# icyradio-exp-mmw-int-rf.net
KiCad netlist of a schematic drawn in EAGLE
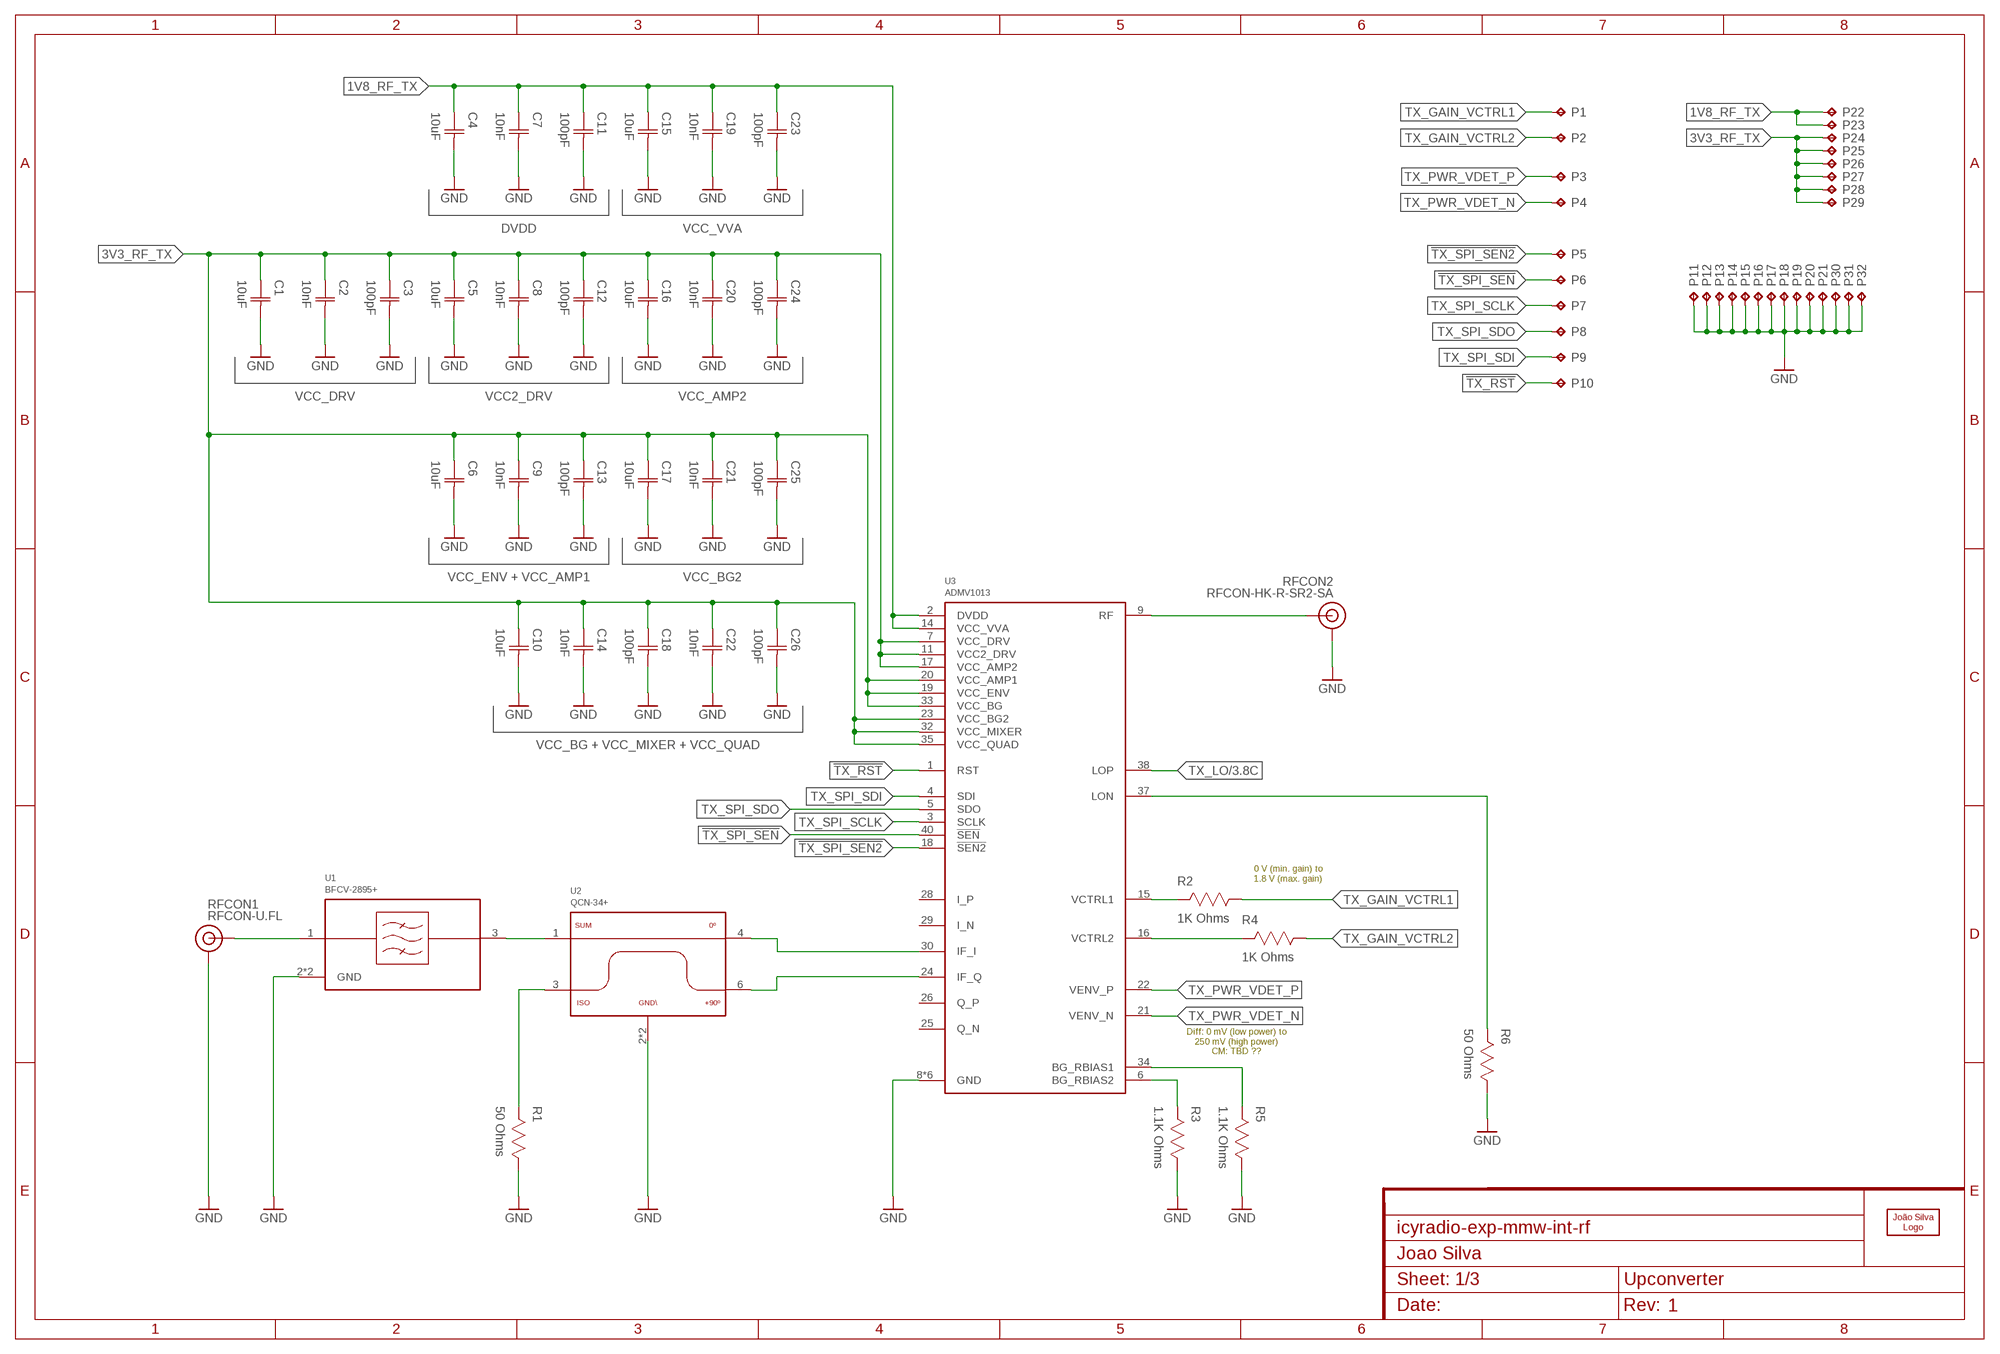
[diagram p0: schematic, sheet 1]
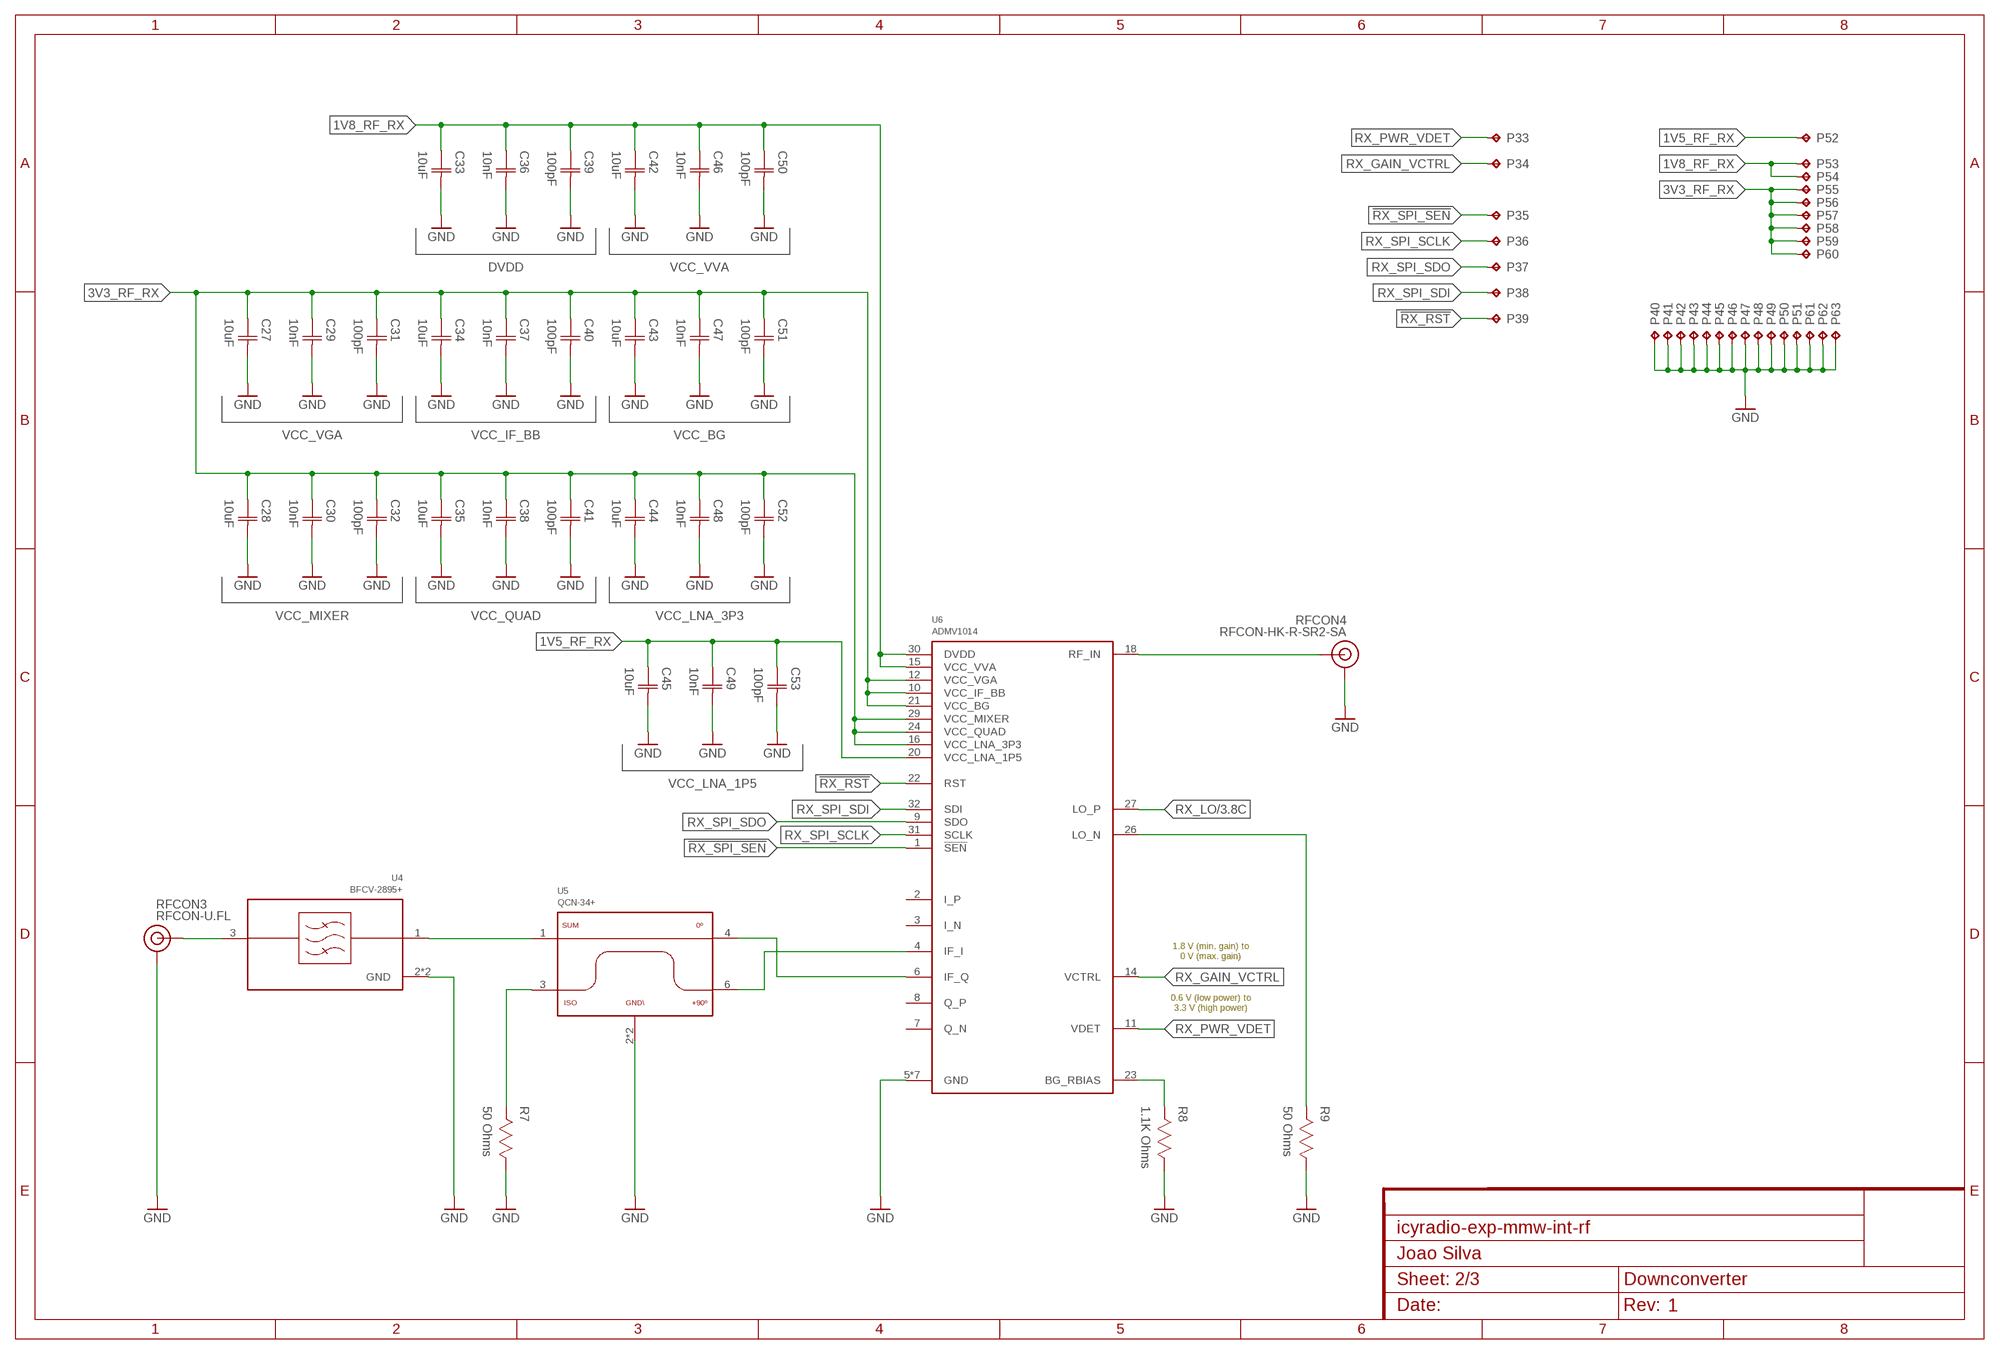
[diagram p1: schematic, sheet 2]
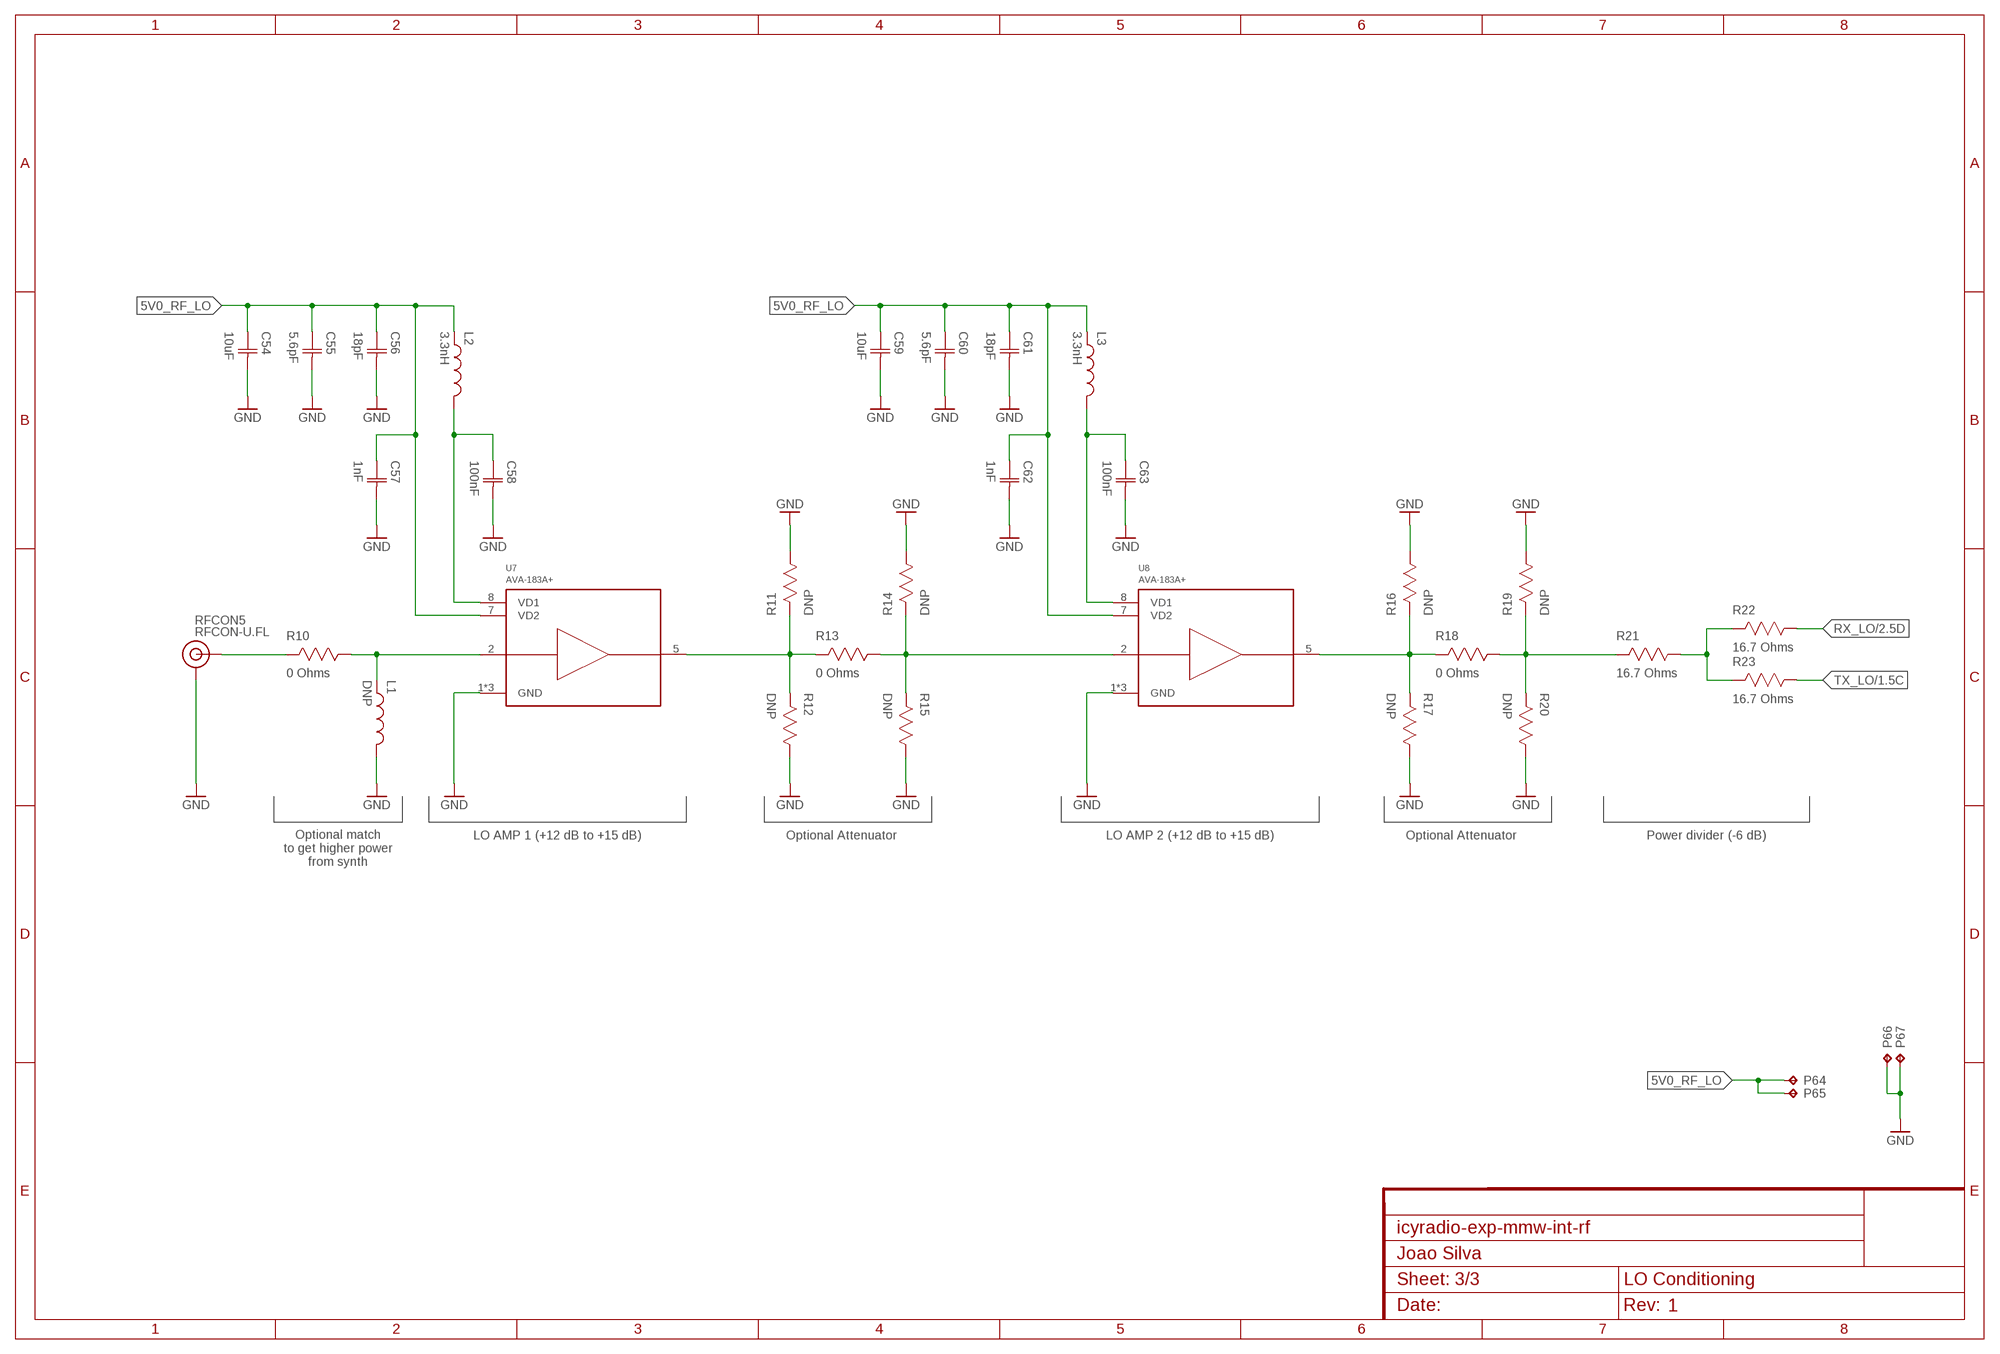
[diagram p2: schematic, sheet 3]

(export (version "E")
  (design (tool "Eeschema 10.0.6"))
  (components
    (comp (ref "C54")
      (value "10uF")
      (footprint "eagle-import:CAP0402")
      (libsource (lib "eagle-import") (part "CAPACITOR-0402"))
    )
    (comp (ref "C55")
      (value "5.6pF")
      (footprint "eagle-import:CAP0402")
      (libsource (lib "eagle-import") (part "CAPACITOR-0402"))
    )
    (comp (ref "C56")
      (value "18pF")
      (footprint "eagle-import:CAP0402")
      (libsource (lib "eagle-import") (part "CAPACITOR-0402"))
    )
    (comp (ref "C57")
      (value "1nF")
      (footprint "eagle-import:CAP0402")
      (libsource (lib "eagle-import") (part "CAPACITOR-0402"))
    )
    (comp (ref "C58")
      (value "100nF")
      (footprint "eagle-import:CAP0402")
      (libsource (lib "eagle-import") (part "CAPACITOR-0402"))
    )
    (comp (ref "C59")
      (value "10uF")
      (footprint "eagle-import:CAP0402")
      (libsource (lib "eagle-import") (part "CAPACITOR-0402"))
    )
    (comp (ref "C60")
      (value "5.6pF")
      (footprint "eagle-import:CAP0402")
      (libsource (lib "eagle-import") (part "CAPACITOR-0402"))
    )
    (comp (ref "C61")
      (value "18pF")
      (footprint "eagle-import:CAP0402")
      (libsource (lib "eagle-import") (part "CAPACITOR-0402"))
    )
    (comp (ref "C62")
      (value "1nF")
      (footprint "eagle-import:CAP0402")
      (libsource (lib "eagle-import") (part "CAPACITOR-0402"))
    )
    (comp (ref "C63")
      (value "100nF")
      (footprint "eagle-import:CAP0402")
      (libsource (lib "eagle-import") (part "CAPACITOR-0402"))
    )
    (comp (ref "L1")
      (value "DNP")
      (footprint "eagle-import:IND0402")
      (libsource (lib "eagle-import") (part "INDUCTOR-0402"))
    )
    (comp (ref "L2")
      (value "3.3nH")
      (footprint "eagle-import:IND0402")
      (libsource (lib "eagle-import") (part "INDUCTOR-0402"))
    )
    (comp (ref "L3")
      (value "3.3nH")
      (footprint "eagle-import:IND0402")
      (libsource (lib "eagle-import") (part "INDUCTOR-0402"))
    )
    (comp (ref "P64")
      (value "CHOLE-0.9MM-SS")
      (footprint "eagle-import:CAST_HOLE_0P9MM_SS")
      (libsource (lib "eagle-import") (part "CHOLE-0.9MM-SS"))
    )
    (comp (ref "P65")
      (value "CHOLE-0.9MM-SS")
      (footprint "eagle-import:CAST_HOLE_0P9MM_SS")
      (libsource (lib "eagle-import") (part "CHOLE-0.9MM-SS"))
    )
    (comp (ref "P66")
      (value "CHOLE-0.9MM-DS")
      (footprint "eagle-import:CAST_HOLE_0P9MM_DS")
      (libsource (lib "eagle-import") (part "CHOLE-0.9MM-DS"))
    )
    (comp (ref "P67")
      (value "CHOLE-0.9MM-DS")
      (footprint "eagle-import:CAST_HOLE_0P9MM_DS")
      (libsource (lib "eagle-import") (part "CHOLE-0.9MM-DS"))
    )
    (comp (ref "R10")
      (value "0 Ohms")
      (footprint "eagle-import:RES0402")
      (libsource (lib "eagle-import") (part "RESISTOR-0402"))
    )
    (comp (ref "R11")
      (value "DNP")
      (footprint "eagle-import:RES0402")
      (libsource (lib "eagle-import") (part "RESISTOR-0402"))
    )
    (comp (ref "R12")
      (value "DNP")
      (footprint "eagle-import:RES0402")
      (libsource (lib "eagle-import") (part "RESISTOR-0402"))
    )
    (comp (ref "R13")
      (value "0 Ohms")
      (footprint "eagle-import:RES0402")
      (libsource (lib "eagle-import") (part "RESISTOR-0402"))
    )
    (comp (ref "R14")
      (value "DNP")
      (footprint "eagle-import:RES0402")
      (libsource (lib "eagle-import") (part "RESISTOR-0402"))
    )
    (comp (ref "R15")
      (value "DNP")
      (footprint "eagle-import:RES0402")
      (libsource (lib "eagle-import") (part "RESISTOR-0402"))
    )
    (comp (ref "R16")
      (value "DNP")
      (footprint "eagle-import:RES0402")
      (libsource (lib "eagle-import") (part "RESISTOR-0402"))
    )
    (comp (ref "R17")
      (value "DNP")
      (footprint "eagle-import:RES0402")
      (libsource (lib "eagle-import") (part "RESISTOR-0402"))
    )
    (comp (ref "R18")
      (value "0 Ohms")
      (footprint "eagle-import:RES0402")
      (libsource (lib "eagle-import") (part "RESISTOR-0402"))
    )
    (comp (ref "R19")
      (value "DNP")
      (footprint "eagle-import:RES0402")
      (libsource (lib "eagle-import") (part "RESISTOR-0402"))
    )
    (comp (ref "R20")
      (value "DNP")
      (footprint "eagle-import:RES0402")
      (libsource (lib "eagle-import") (part "RESISTOR-0402"))
    )
    (comp (ref "R21")
      (value "16.7 Ohms")
      (footprint "eagle-import:RES0402")
      (libsource (lib "eagle-import") (part "RESISTOR-0402"))
    )
    (comp (ref "R22")
      (value "16.7 Ohms")
      (footprint "eagle-import:RES0402")
      (libsource (lib "eagle-import") (part "RESISTOR-0402"))
    )
    (comp (ref "R23")
      (value "16.7 Ohms")
      (footprint "eagle-import:RES0402")
      (libsource (lib "eagle-import") (part "RESISTOR-0402"))
    )
    (comp (ref "RFCON5")
      (value "RFCON-U.FL")
      (footprint "eagle-import:U.FL")
      (libsource (lib "eagle-import") (part "RFCON-U.FL"))
    )
    (comp (ref "U7")
      (value "AVA-183A+")
      (footprint "eagle-import:DQ849")
      (libsource (lib "eagle-import") (part "AVA-183A+"))
    )
    (comp (ref "U8")
      (value "AVA-183A+")
      (footprint "eagle-import:DQ849")
      (libsource (lib "eagle-import") (part "AVA-183A+"))
    )
    (comp (ref "C1")
      (value "10uF")
      (footprint "eagle-import:CAP0402")
      (libsource (lib "eagle-import") (part "CAPACITOR-0402"))
    )
    (comp (ref "C2")
      (value "10nF")
      (footprint "eagle-import:CAP0402")
      (libsource (lib "eagle-import") (part "CAPACITOR-0402"))
    )
    (comp (ref "C3")
      (value "100pF")
      (footprint "eagle-import:CAP0402")
      (libsource (lib "eagle-import") (part "CAPACITOR-0402"))
    )
    (comp (ref "C4")
      (value "10uF")
      (footprint "eagle-import:CAP0402")
      (libsource (lib "eagle-import") (part "CAPACITOR-0402"))
    )
    (comp (ref "C5")
      (value "10uF")
      (footprint "eagle-import:CAP0402")
      (libsource (lib "eagle-import") (part "CAPACITOR-0402"))
    )
    (comp (ref "C6")
      (value "10uF")
      (footprint "eagle-import:CAP0402")
      (libsource (lib "eagle-import") (part "CAPACITOR-0402"))
    )
    (comp (ref "C7")
      (value "10nF")
      (footprint "eagle-import:CAP0402")
      (libsource (lib "eagle-import") (part "CAPACITOR-0402"))
    )
    (comp (ref "C8")
      (value "10nF")
      (footprint "eagle-import:CAP0402")
      (libsource (lib "eagle-import") (part "CAPACITOR-0402"))
    )
    (comp (ref "C9")
      (value "10nF")
      (footprint "eagle-import:CAP0402")
      (libsource (lib "eagle-import") (part "CAPACITOR-0402"))
    )
    (comp (ref "C10")
      (value "10uF")
      (footprint "eagle-import:CAP0402")
      (libsource (lib "eagle-import") (part "CAPACITOR-0402"))
    )
    (comp (ref "C11")
      (value "100pF")
      (footprint "eagle-import:CAP0402")
      (libsource (lib "eagle-import") (part "CAPACITOR-0402"))
    )
    (comp (ref "C12")
      (value "100pF")
      (footprint "eagle-import:CAP0402")
      (libsource (lib "eagle-import") (part "CAPACITOR-0402"))
    )
    (comp (ref "C13")
      (value "100pF")
      (footprint "eagle-import:CAP0402")
      (libsource (lib "eagle-import") (part "CAPACITOR-0402"))
    )
    (comp (ref "C14")
      (value "10nF")
      (footprint "eagle-import:CAP0402")
      (libsource (lib "eagle-import") (part "CAPACITOR-0402"))
    )
    (comp (ref "C15")
      (value "10uF")
      (footprint "eagle-import:CAP0402")
      (libsource (lib "eagle-import") (part "CAPACITOR-0402"))
    )
    (comp (ref "C16")
      (value "10uF")
      (footprint "eagle-import:CAP0402")
      (libsource (lib "eagle-import") (part "CAPACITOR-0402"))
    )
    (comp (ref "C17")
      (value "10uF")
      (footprint "eagle-import:CAP0402")
      (libsource (lib "eagle-import") (part "CAPACITOR-0402"))
    )
    (comp (ref "C18")
      (value "100pF")
      (footprint "eagle-import:CAP0402")
      (libsource (lib "eagle-import") (part "CAPACITOR-0402"))
    )
    (comp (ref "C19")
      (value "10nF")
      (footprint "eagle-import:CAP0402")
      (libsource (lib "eagle-import") (part "CAPACITOR-0402"))
    )
    (comp (ref "C20")
      (value "10nF")
      (footprint "eagle-import:CAP0402")
      (libsource (lib "eagle-import") (part "CAPACITOR-0402"))
    )
    (comp (ref "C21")
      (value "10nF")
      (footprint "eagle-import:CAP0402")
      (libsource (lib "eagle-import") (part "CAPACITOR-0402"))
    )
    (comp (ref "C22")
      (value "10nF")
      (footprint "eagle-import:CAP0402")
      (libsource (lib "eagle-import") (part "CAPACITOR-0402"))
    )
    (comp (ref "C23")
      (value "100pF")
      (footprint "eagle-import:CAP0402")
      (libsource (lib "eagle-import") (part "CAPACITOR-0402"))
    )
    (comp (ref "C24")
      (value "100pF")
      (footprint "eagle-import:CAP0402")
      (libsource (lib "eagle-import") (part "CAPACITOR-0402"))
    )
    (comp (ref "C25")
      (value "100pF")
      (footprint "eagle-import:CAP0402")
      (libsource (lib "eagle-import") (part "CAPACITOR-0402"))
    )
    (comp (ref "C26")
      (value "100pF")
      (footprint "eagle-import:CAP0402")
      (libsource (lib "eagle-import") (part "CAPACITOR-0402"))
    )
    (comp (ref "LOGO1")
      (value "JSILVA-5MM")
      (footprint "eagle-import:JSILVA_5MM")
      (libsource (lib "eagle-import") (part "JSILVA-5MM"))
    )
    (comp (ref "P1")
      (value "CHOLE-0.9MM-SS")
      (footprint "eagle-import:CAST_HOLE_0P9MM_SS")
      (libsource (lib "eagle-import") (part "CHOLE-0.9MM-SS"))
    )
    (comp (ref "P2")
      (value "CHOLE-0.9MM-SS")
      (footprint "eagle-import:CAST_HOLE_0P9MM_SS")
      (libsource (lib "eagle-import") (part "CHOLE-0.9MM-SS"))
    )
    (comp (ref "P3")
      (value "CHOLE-0.9MM-SS")
      (footprint "eagle-import:CAST_HOLE_0P9MM_SS")
      (libsource (lib "eagle-import") (part "CHOLE-0.9MM-SS"))
    )
    (comp (ref "P4")
      (value "CHOLE-0.9MM-SS")
      (footprint "eagle-import:CAST_HOLE_0P9MM_SS")
      (libsource (lib "eagle-import") (part "CHOLE-0.9MM-SS"))
    )
    (comp (ref "P5")
      (value "CHOLE-0.9MM-SS")
      (footprint "eagle-import:CAST_HOLE_0P9MM_SS")
      (libsource (lib "eagle-import") (part "CHOLE-0.9MM-SS"))
    )
    (comp (ref "P6")
      (value "CHOLE-0.9MM-SS")
      (footprint "eagle-import:CAST_HOLE_0P9MM_SS")
      (libsource (lib "eagle-import") (part "CHOLE-0.9MM-SS"))
    )
    (comp (ref "P7")
      (value "CHOLE-0.9MM-SS")
      (footprint "eagle-import:CAST_HOLE_0P9MM_SS")
      (libsource (lib "eagle-import") (part "CHOLE-0.9MM-SS"))
    )
    (comp (ref "P8")
      (value "CHOLE-0.9MM-SS")
      (footprint "eagle-import:CAST_HOLE_0P9MM_SS")
      (libsource (lib "eagle-import") (part "CHOLE-0.9MM-SS"))
    )
    (comp (ref "P9")
      (value "CHOLE-0.9MM-SS")
      (footprint "eagle-import:CAST_HOLE_0P9MM_SS")
      (libsource (lib "eagle-import") (part "CHOLE-0.9MM-SS"))
    )
    (comp (ref "P10")
      (value "CHOLE-0.9MM-SS")
      (footprint "eagle-import:CAST_HOLE_0P9MM_SS")
      (libsource (lib "eagle-import") (part "CHOLE-0.9MM-SS"))
    )
    (comp (ref "P11")
      (value "CHOLE-0.9MM-DS")
      (footprint "eagle-import:CAST_HOLE_0P9MM_DS")
      (libsource (lib "eagle-import") (part "CHOLE-0.9MM-DS"))
    )
    (comp (ref "P12")
      (value "CHOLE-0.9MM-DS")
      (footprint "eagle-import:CAST_HOLE_0P9MM_DS")
      (libsource (lib "eagle-import") (part "CHOLE-0.9MM-DS"))
    )
    (comp (ref "P13")
      (value "CHOLE-0.9MM-DS")
      (footprint "eagle-import:CAST_HOLE_0P9MM_DS")
      (libsource (lib "eagle-import") (part "CHOLE-0.9MM-DS"))
    )
    (comp (ref "P14")
      (value "CHOLE-0.9MM-DS")
      (footprint "eagle-import:CAST_HOLE_0P9MM_DS")
      (libsource (lib "eagle-import") (part "CHOLE-0.9MM-DS"))
    )
    (comp (ref "P15")
      (value "CHOLE-0.9MM-DS")
      (footprint "eagle-import:CAST_HOLE_0P9MM_DS")
      (libsource (lib "eagle-import") (part "CHOLE-0.9MM-DS"))
    )
    (comp (ref "P16")
      (value "CHOLE-0.9MM-DS")
      (footprint "eagle-import:CAST_HOLE_0P9MM_DS")
      (libsource (lib "eagle-import") (part "CHOLE-0.9MM-DS"))
    )
    (comp (ref "P17")
      (value "CHOLE-0.9MM-DS")
      (footprint "eagle-import:CAST_HOLE_0P9MM_DS")
      (libsource (lib "eagle-import") (part "CHOLE-0.9MM-DS"))
    )
    (comp (ref "P18")
      (value "CHOLE-0.9MM-DS")
      (footprint "eagle-import:CAST_HOLE_0P9MM_DS")
      (libsource (lib "eagle-import") (part "CHOLE-0.9MM-DS"))
    )
    (comp (ref "P19")
      (value "CHOLE-0.9MM-DS")
      (footprint "eagle-import:CAST_HOLE_0P9MM_DS")
      (libsource (lib "eagle-import") (part "CHOLE-0.9MM-DS"))
    )
    (comp (ref "P20")
      (value "CHOLE-0.9MM-DS")
      (footprint "eagle-import:CAST_HOLE_0P9MM_DS")
      (libsource (lib "eagle-import") (part "CHOLE-0.9MM-DS"))
    )
    (comp (ref "P21")
      (value "CHOLE-0.9MM-DS")
      (footprint "eagle-import:CAST_HOLE_0P9MM_DS")
      (libsource (lib "eagle-import") (part "CHOLE-0.9MM-DS"))
    )
    (comp (ref "P22")
      (value "CHOLE-0.9MM-SS")
      (footprint "eagle-import:CAST_HOLE_0P9MM_SS")
      (libsource (lib "eagle-import") (part "CHOLE-0.9MM-SS"))
    )
    (comp (ref "P23")
      (value "CHOLE-0.9MM-SS")
      (footprint "eagle-import:CAST_HOLE_0P9MM_SS")
      (libsource (lib "eagle-import") (part "CHOLE-0.9MM-SS"))
    )
    (comp (ref "P24")
      (value "CHOLE-0.9MM-SS")
      (footprint "eagle-import:CAST_HOLE_0P9MM_SS")
      (libsource (lib "eagle-import") (part "CHOLE-0.9MM-SS"))
    )
    (comp (ref "P25")
      (value "CHOLE-0.9MM-SS")
      (footprint "eagle-import:CAST_HOLE_0P9MM_SS")
      (libsource (lib "eagle-import") (part "CHOLE-0.9MM-SS"))
    )
    (comp (ref "P26")
      (value "CHOLE-0.9MM-SS")
      (footprint "eagle-import:CAST_HOLE_0P9MM_SS")
      (libsource (lib "eagle-import") (part "CHOLE-0.9MM-SS"))
    )
    (comp (ref "P27")
      (value "CHOLE-0.9MM-SS")
      (footprint "eagle-import:CAST_HOLE_0P9MM_SS")
      (libsource (lib "eagle-import") (part "CHOLE-0.9MM-SS"))
    )
    (comp (ref "P28")
      (value "CHOLE-0.9MM-SS")
      (footprint "eagle-import:CAST_HOLE_0P9MM_SS")
      (libsource (lib "eagle-import") (part "CHOLE-0.9MM-SS"))
    )
    (comp (ref "P29")
      (value "CHOLE-0.9MM-SS")
      (footprint "eagle-import:CAST_HOLE_0P9MM_SS")
      (libsource (lib "eagle-import") (part "CHOLE-0.9MM-SS"))
    )
    (comp (ref "P30")
      (value "CHOLE-0.9MM-DS")
      (footprint "eagle-import:CAST_HOLE_0P9MM_DS")
      (libsource (lib "eagle-import") (part "CHOLE-0.9MM-DS"))
    )
    (comp (ref "P31")
      (value "CHOLE-0.9MM-DS")
      (footprint "eagle-import:CAST_HOLE_0P9MM_DS")
      (libsource (lib "eagle-import") (part "CHOLE-0.9MM-DS"))
    )
    (comp (ref "P32")
      (value "CHOLE-0.9MM-DS")
      (footprint "eagle-import:CAST_HOLE_0P9MM_DS")
      (libsource (lib "eagle-import") (part "CHOLE-0.9MM-DS"))
    )
    (comp (ref "R1")
      (value "50 Ohms")
      (footprint "eagle-import:RES0402")
      (libsource (lib "eagle-import") (part "RESISTOR-0402"))
    )
    (comp (ref "R2")
      (value "1K Ohms")
      (footprint "eagle-import:RES0402")
      (libsource (lib "eagle-import") (part "RESISTOR-0402"))
    )
    (comp (ref "R3")
      (value "1.1K Ohms")
      (footprint "eagle-import:RES0402")
      (libsource (lib "eagle-import") (part "RESISTOR-0402"))
    )
    (comp (ref "R4")
      (value "1K Ohms")
      (footprint "eagle-import:RES0402")
      (libsource (lib "eagle-import") (part "RESISTOR-0402"))
    )
    (comp (ref "R5")
      (value "1.1K Ohms")
      (footprint "eagle-import:RES0402")
      (libsource (lib "eagle-import") (part "RESISTOR-0402"))
    )
    (comp (ref "R6")
      (value "50 Ohms")
      (footprint "eagle-import:RES0402")
      (libsource (lib "eagle-import") (part "RESISTOR-0402"))
    )
    (comp (ref "RFCON1")
      (value "RFCON-U.FL")
      (footprint "eagle-import:U.FL")
      (libsource (lib "eagle-import") (part "RFCON-U.FL"))
    )
    (comp (ref "RFCON2")
      (value "RFCON-HK-R-SR2-SA")
      (footprint "eagle-import:HK-R-SR2-SA")
      (libsource (lib "eagle-import") (part "RFCON-HK-R-SR2-SA"))
    )
    (comp (ref "U1")
      (value "BFCV-2895+")
      (footprint "eagle-import:JV1210C")
      (libsource (lib "eagle-import") (part "BFCV-+2895"))
    )
    (comp (ref "U2")
      (value "QCN-34+")
      (footprint "eagle-import:FV1206-1")
      (libsource (lib "eagle-import") (part "QCN-34+"))
    )
    (comp (ref "U3")
      (value "ADMV1013")
      (footprint "eagle-import:LGA40")
      (libsource (lib "eagle-import") (part "ADMV1013"))
    )
    (comp (ref "C27")
      (value "10uF")
      (footprint "eagle-import:CAP0402")
      (libsource (lib "eagle-import") (part "CAPACITOR-0402"))
    )
    (comp (ref "C28")
      (value "10uF")
      (footprint "eagle-import:CAP0402")
      (libsource (lib "eagle-import") (part "CAPACITOR-0402"))
    )
    (comp (ref "C29")
      (value "10nF")
      (footprint "eagle-import:CAP0402")
      (libsource (lib "eagle-import") (part "CAPACITOR-0402"))
    )
    (comp (ref "C30")
      (value "10nF")
      (footprint "eagle-import:CAP0402")
      (libsource (lib "eagle-import") (part "CAPACITOR-0402"))
    )
    (comp (ref "C31")
      (value "100pF")
      (footprint "eagle-import:CAP0402")
      (libsource (lib "eagle-import") (part "CAPACITOR-0402"))
    )
    (comp (ref "C32")
      (value "100pF")
      (footprint "eagle-import:CAP0402")
      (libsource (lib "eagle-import") (part "CAPACITOR-0402"))
    )
    (comp (ref "C33")
      (value "10uF")
      (footprint "eagle-import:CAP0402")
      (libsource (lib "eagle-import") (part "CAPACITOR-0402"))
    )
    (comp (ref "C34")
      (value "10uF")
      (footprint "eagle-import:CAP0402")
      (libsource (lib "eagle-import") (part "CAPACITOR-0402"))
    )
    (comp (ref "C35")
      (value "10uF")
      (footprint "eagle-import:CAP0402")
      (libsource (lib "eagle-import") (part "CAPACITOR-0402"))
    )
    (comp (ref "C36")
      (value "10nF")
      (footprint "eagle-import:CAP0402")
      (libsource (lib "eagle-import") (part "CAPACITOR-0402"))
    )
    (comp (ref "C37")
      (value "10nF")
      (footprint "eagle-import:CAP0402")
      (libsource (lib "eagle-import") (part "CAPACITOR-0402"))
    )
    (comp (ref "C38")
      (value "10nF")
      (footprint "eagle-import:CAP0402")
      (libsource (lib "eagle-import") (part "CAPACITOR-0402"))
    )
    (comp (ref "C39")
      (value "100pF")
      (footprint "eagle-import:CAP0402")
      (libsource (lib "eagle-import") (part "CAPACITOR-0402"))
    )
    (comp (ref "C40")
      (value "100pF")
      (footprint "eagle-import:CAP0402")
      (libsource (lib "eagle-import") (part "CAPACITOR-0402"))
    )
    (comp (ref "C41")
      (value "100pF")
      (footprint "eagle-import:CAP0402")
      (libsource (lib "eagle-import") (part "CAPACITOR-0402"))
    )
    (comp (ref "C42")
      (value "10uF")
      (footprint "eagle-import:CAP0402")
      (libsource (lib "eagle-import") (part "CAPACITOR-0402"))
    )
    (comp (ref "C43")
      (value "10uF")
      (footprint "eagle-import:CAP0402")
      (libsource (lib "eagle-import") (part "CAPACITOR-0402"))
    )
    (comp (ref "C44")
      (value "10uF")
      (footprint "eagle-import:CAP0402")
      (libsource (lib "eagle-import") (part "CAPACITOR-0402"))
    )
    (comp (ref "C45")
      (value "10uF")
      (footprint "eagle-import:CAP0402")
      (libsource (lib "eagle-import") (part "CAPACITOR-0402"))
    )
    (comp (ref "C46")
      (value "10nF")
      (footprint "eagle-import:CAP0402")
      (libsource (lib "eagle-import") (part "CAPACITOR-0402"))
    )
    (comp (ref "C47")
      (value "10nF")
      (footprint "eagle-import:CAP0402")
      (libsource (lib "eagle-import") (part "CAPACITOR-0402"))
    )
    (comp (ref "C48")
      (value "10nF")
      (footprint "eagle-import:CAP0402")
      (libsource (lib "eagle-import") (part "CAPACITOR-0402"))
    )
    (comp (ref "C49")
      (value "10nF")
      (footprint "eagle-import:CAP0402")
      (libsource (lib "eagle-import") (part "CAPACITOR-0402"))
    )
    (comp (ref "C50")
      (value "100pF")
      (footprint "eagle-import:CAP0402")
      (libsource (lib "eagle-import") (part "CAPACITOR-0402"))
    )
    (comp (ref "C51")
      (value "100pF")
      (footprint "eagle-import:CAP0402")
      (libsource (lib "eagle-import") (part "CAPACITOR-0402"))
    )
    (comp (ref "C52")
      (value "100pF")
      (footprint "eagle-import:CAP0402")
      (libsource (lib "eagle-import") (part "CAPACITOR-0402"))
    )
    (comp (ref "C53")
      (value "100pF")
      (footprint "eagle-import:CAP0402")
      (libsource (lib "eagle-import") (part "CAPACITOR-0402"))
    )
    (comp (ref "P33")
      (value "CHOLE-0.9MM-SS")
      (footprint "eagle-import:CAST_HOLE_0P9MM_SS")
      (libsource (lib "eagle-import") (part "CHOLE-0.9MM-SS"))
    )
    (comp (ref "P34")
      (value "CHOLE-0.9MM-SS")
      (footprint "eagle-import:CAST_HOLE_0P9MM_SS")
      (libsource (lib "eagle-import") (part "CHOLE-0.9MM-SS"))
    )
    (comp (ref "P35")
      (value "CHOLE-0.9MM-SS")
      (footprint "eagle-import:CAST_HOLE_0P9MM_SS")
      (libsource (lib "eagle-import") (part "CHOLE-0.9MM-SS"))
    )
    (comp (ref "P36")
      (value "CHOLE-0.9MM-SS")
      (footprint "eagle-import:CAST_HOLE_0P9MM_SS")
      (libsource (lib "eagle-import") (part "CHOLE-0.9MM-SS"))
    )
    (comp (ref "P37")
      (value "CHOLE-0.9MM-SS")
      (footprint "eagle-import:CAST_HOLE_0P9MM_SS")
      (libsource (lib "eagle-import") (part "CHOLE-0.9MM-SS"))
    )
    (comp (ref "P38")
      (value "CHOLE-0.9MM-SS")
      (footprint "eagle-import:CAST_HOLE_0P9MM_SS")
      (libsource (lib "eagle-import") (part "CHOLE-0.9MM-SS"))
    )
    (comp (ref "P39")
      (value "CHOLE-0.9MM-SS")
      (footprint "eagle-import:CAST_HOLE_0P9MM_SS")
      (libsource (lib "eagle-import") (part "CHOLE-0.9MM-SS"))
    )
    (comp (ref "P40")
      (value "CHOLE-0.9MM-DS")
      (footprint "eagle-import:CAST_HOLE_0P9MM_DS")
      (libsource (lib "eagle-import") (part "CHOLE-0.9MM-DS"))
    )
    (comp (ref "P41")
      (value "CHOLE-0.9MM-DS")
      (footprint "eagle-import:CAST_HOLE_0P9MM_DS")
      (libsource (lib "eagle-import") (part "CHOLE-0.9MM-DS"))
    )
    (comp (ref "P42")
      (value "CHOLE-0.9MM-DS")
      (footprint "eagle-import:CAST_HOLE_0P9MM_DS")
      (libsource (lib "eagle-import") (part "CHOLE-0.9MM-DS"))
    )
    (comp (ref "P43")
      (value "CHOLE-0.9MM-DS")
      (footprint "eagle-import:CAST_HOLE_0P9MM_DS")
      (libsource (lib "eagle-import") (part "CHOLE-0.9MM-DS"))
    )
    (comp (ref "P44")
      (value "CHOLE-0.9MM-DS")
      (footprint "eagle-import:CAST_HOLE_0P9MM_DS")
      (libsource (lib "eagle-import") (part "CHOLE-0.9MM-DS"))
    )
    (comp (ref "P45")
      (value "CHOLE-0.9MM-DS")
      (footprint "eagle-import:CAST_HOLE_0P9MM_DS")
      (libsource (lib "eagle-import") (part "CHOLE-0.9MM-DS"))
    )
    (comp (ref "P46")
      (value "CHOLE-0.9MM-DS")
      (footprint "eagle-import:CAST_HOLE_0P9MM_DS")
      (libsource (lib "eagle-import") (part "CHOLE-0.9MM-DS"))
    )
    (comp (ref "P47")
      (value "CHOLE-0.9MM-DS")
      (footprint "eagle-import:CAST_HOLE_0P9MM_DS")
      (libsource (lib "eagle-import") (part "CHOLE-0.9MM-DS"))
    )
    (comp (ref "P48")
      (value "CHOLE-0.9MM-DS")
      (footprint "eagle-import:CAST_HOLE_0P9MM_DS")
      (libsource (lib "eagle-import") (part "CHOLE-0.9MM-DS"))
    )
    (comp (ref "P49")
      (value "CHOLE-0.9MM-DS")
      (footprint "eagle-import:CAST_HOLE_0P9MM_DS")
      (libsource (lib "eagle-import") (part "CHOLE-0.9MM-DS"))
    )
    (comp (ref "P50")
      (value "CHOLE-0.9MM-DS")
      (footprint "eagle-import:CAST_HOLE_0P9MM_DS")
      (libsource (lib "eagle-import") (part "CHOLE-0.9MM-DS"))
    )
    (comp (ref "P51")
      (value "CHOLE-0.9MM-DS")
      (footprint "eagle-import:CAST_HOLE_0P9MM_DS")
      (libsource (lib "eagle-import") (part "CHOLE-0.9MM-DS"))
    )
    (comp (ref "P52")
      (value "CHOLE-0.9MM-SS")
      (footprint "eagle-import:CAST_HOLE_0P9MM_SS")
      (libsource (lib "eagle-import") (part "CHOLE-0.9MM-SS"))
    )
    (comp (ref "P53")
      (value "CHOLE-0.9MM-SS")
      (footprint "eagle-import:CAST_HOLE_0P9MM_SS")
      (libsource (lib "eagle-import") (part "CHOLE-0.9MM-SS"))
    )
    (comp (ref "P54")
      (value "CHOLE-0.9MM-SS")
      (footprint "eagle-import:CAST_HOLE_0P9MM_SS")
      (libsource (lib "eagle-import") (part "CHOLE-0.9MM-SS"))
    )
    (comp (ref "P55")
      (value "CHOLE-0.9MM-SS")
      (footprint "eagle-import:CAST_HOLE_0P9MM_SS")
      (libsource (lib "eagle-import") (part "CHOLE-0.9MM-SS"))
    )
    (comp (ref "P56")
      (value "CHOLE-0.9MM-SS")
      (footprint "eagle-import:CAST_HOLE_0P9MM_SS")
      (libsource (lib "eagle-import") (part "CHOLE-0.9MM-SS"))
    )
    (comp (ref "P57")
      (value "CHOLE-0.9MM-SS")
      (footprint "eagle-import:CAST_HOLE_0P9MM_SS")
      (libsource (lib "eagle-import") (part "CHOLE-0.9MM-SS"))
    )
    (comp (ref "P58")
      (value "CHOLE-0.9MM-SS")
      (footprint "eagle-import:CAST_HOLE_0P9MM_SS")
      (libsource (lib "eagle-import") (part "CHOLE-0.9MM-SS"))
    )
    (comp (ref "P59")
      (value "CHOLE-0.9MM-SS")
      (footprint "eagle-import:CAST_HOLE_0P9MM_SS")
      (libsource (lib "eagle-import") (part "CHOLE-0.9MM-SS"))
    )
    (comp (ref "P60")
      (value "CHOLE-0.9MM-SS")
      (footprint "eagle-import:CAST_HOLE_0P9MM_SS")
      (libsource (lib "eagle-import") (part "CHOLE-0.9MM-SS"))
    )
    (comp (ref "P61")
      (value "CHOLE-0.9MM-DS")
      (footprint "eagle-import:CAST_HOLE_0P9MM_DS")
      (libsource (lib "eagle-import") (part "CHOLE-0.9MM-DS"))
    )
    (comp (ref "P62")
      (value "CHOLE-0.9MM-DS")
      (footprint "eagle-import:CAST_HOLE_0P9MM_DS")
      (libsource (lib "eagle-import") (part "CHOLE-0.9MM-DS"))
    )
    (comp (ref "P63")
      (value "CHOLE-0.9MM-DS")
      (footprint "eagle-import:CAST_HOLE_0P9MM_DS")
      (libsource (lib "eagle-import") (part "CHOLE-0.9MM-DS"))
    )
    (comp (ref "R7")
      (value "50 Ohms")
      (footprint "eagle-import:RES0402")
      (libsource (lib "eagle-import") (part "RESISTOR-0402"))
    )
    (comp (ref "R8")
      (value "1.1K Ohms")
      (footprint "eagle-import:RES0402")
      (libsource (lib "eagle-import") (part "RESISTOR-0402"))
    )
    (comp (ref "R9")
      (value "50 Ohms")
      (footprint "eagle-import:RES0402")
      (libsource (lib "eagle-import") (part "RESISTOR-0402"))
    )
    (comp (ref "RFCON3")
      (value "RFCON-U.FL")
      (footprint "eagle-import:U.FL")
      (libsource (lib "eagle-import") (part "RFCON-U.FL"))
    )
    (comp (ref "RFCON4")
      (value "RFCON-HK-R-SR2-SA")
      (footprint "eagle-import:HK-R-SR2-SA")
      (libsource (lib "eagle-import") (part "RFCON-HK-R-SR2-SA"))
    )
    (comp (ref "U4")
      (value "BFCV-2895+")
      (footprint "eagle-import:JV1210C")
      (libsource (lib "eagle-import") (part "BFCV-+2895"))
    )
    (comp (ref "U5")
      (value "QCN-34+")
      (footprint "eagle-import:FV1206-1")
      (libsource (lib "eagle-import") (part "QCN-34+"))
    )
    (comp (ref "U6")
      (value "ADMV1014")
      (footprint "eagle-import:LGA32")
      (libsource (lib "eagle-import") (part "ADMV1014"))
    )
  )
  (nets
    (net (code "1") (name "1V5_RF_RX") (class "Default")
      (node (ref "C45") (pin "1") (pinfunction "C1_1") (pintype "passive"))
      (node (ref "C49") (pin "1") (pinfunction "C1_1") (pintype "passive"))
      (node (ref "C53") (pin "1") (pinfunction "C1_1") (pintype "passive"))
      (node (ref "P52") (pin "PAD_T") (pinfunction "TP_PAD_T") (pintype "input"))
      (node (ref "U6") (pin "20") (pinfunction "VCC_LNA_1P5_20") (pintype "power_in"))
    )
    (net (code "2") (name "1V8_RF_RX") (class "Default")
      (node (ref "C33") (pin "1") (pinfunction "C1_1") (pintype "passive"))
      (node (ref "C36") (pin "1") (pinfunction "C1_1") (pintype "passive"))
      (node (ref "C39") (pin "1") (pinfunction "C1_1") (pintype "passive"))
      (node (ref "C42") (pin "1") (pinfunction "C1_1") (pintype "passive"))
      (node (ref "C46") (pin "1") (pinfunction "C1_1") (pintype "passive"))
      (node (ref "C50") (pin "1") (pinfunction "C1_1") (pintype "passive"))
      (node (ref "P53") (pin "PAD_T") (pinfunction "TP_PAD_T") (pintype "input"))
      (node (ref "P54") (pin "PAD_T") (pinfunction "TP_PAD_T") (pintype "input"))
      (node (ref "U6") (pin "15") (pinfunction "VCC_VVA_15") (pintype "power_in"))
      (node (ref "U6") (pin "30") (pinfunction "DVDD_30") (pintype "power_in"))
    )
    (net (code "3") (name "1V8_RF_TX") (class "Default")
      (node (ref "C11") (pin "1") (pinfunction "C1_1") (pintype "passive"))
      (node (ref "C15") (pin "1") (pinfunction "C1_1") (pintype "passive"))
      (node (ref "C19") (pin "1") (pinfunction "C1_1") (pintype "passive"))
      (node (ref "C23") (pin "1") (pinfunction "C1_1") (pintype "passive"))
      (node (ref "C4") (pin "1") (pinfunction "C1_1") (pintype "passive"))
      (node (ref "C7") (pin "1") (pinfunction "C1_1") (pintype "passive"))
      (node (ref "P22") (pin "PAD_T") (pinfunction "TP_PAD_T") (pintype "input"))
      (node (ref "P23") (pin "PAD_T") (pinfunction "TP_PAD_T") (pintype "input"))
      (node (ref "U3") (pin "14") (pinfunction "VCC_VVA_14") (pintype "power_in"))
      (node (ref "U3") (pin "2") (pinfunction "DVDD_2") (pintype "power_in"))
    )
    (net (code "4") (name "3V3_RF_RX") (class "Default")
      (node (ref "C27") (pin "1") (pinfunction "C1_1") (pintype "passive"))
      (node (ref "C28") (pin "1") (pinfunction "C1_1") (pintype "passive"))
      (node (ref "C29") (pin "1") (pinfunction "C1_1") (pintype "passive"))
      (node (ref "C30") (pin "1") (pinfunction "C1_1") (pintype "passive"))
      (node (ref "C31") (pin "1") (pinfunction "C1_1") (pintype "passive"))
      (node (ref "C32") (pin "1") (pinfunction "C1_1") (pintype "passive"))
      (node (ref "C34") (pin "1") (pinfunction "C1_1") (pintype "passive"))
      (node (ref "C35") (pin "1") (pinfunction "C1_1") (pintype "passive"))
      (node (ref "C37") (pin "1") (pinfunction "C1_1") (pintype "passive"))
      (node (ref "C38") (pin "1") (pinfunction "C1_1") (pintype "passive"))
      (node (ref "C40") (pin "1") (pinfunction "C1_1") (pintype "passive"))
      (node (ref "C41") (pin "1") (pinfunction "C1_1") (pintype "passive"))
      (node (ref "C43") (pin "1") (pinfunction "C1_1") (pintype "passive"))
      (node (ref "C44") (pin "1") (pinfunction "C1_1") (pintype "passive"))
      (node (ref "C47") (pin "1") (pinfunction "C1_1") (pintype "passive"))
      (node (ref "C48") (pin "1") (pinfunction "C1_1") (pintype "passive"))
      (node (ref "C51") (pin "1") (pinfunction "C1_1") (pintype "passive"))
      (node (ref "C52") (pin "1") (pinfunction "C1_1") (pintype "passive"))
      (node (ref "P55") (pin "PAD_T") (pinfunction "TP_PAD_T") (pintype "input"))
      (node (ref "P56") (pin "PAD_T") (pinfunction "TP_PAD_T") (pintype "input"))
      (node (ref "P57") (pin "PAD_T") (pinfunction "TP_PAD_T") (pintype "input"))
      (node (ref "P58") (pin "PAD_T") (pinfunction "TP_PAD_T") (pintype "input"))
      (node (ref "P59") (pin "PAD_T") (pinfunction "TP_PAD_T") (pintype "input"))
      (node (ref "P60") (pin "PAD_T") (pinfunction "TP_PAD_T") (pintype "input"))
      (node (ref "U6") (pin "10") (pinfunction "VCC_IF_BB_10") (pintype "power_in"))
      (node (ref "U6") (pin "12") (pinfunction "VCC_VGA_12") (pintype "power_in"))
      (node (ref "U6") (pin "16") (pinfunction "VCC_LNA_3P3_16") (pintype "power_in"))
      (node (ref "U6") (pin "21") (pinfunction "VCC_BG_21") (pintype "power_in"))
      (node (ref "U6") (pin "24") (pinfunction "VCC_QUAD_24") (pintype "power_in"))
      (node (ref "U6") (pin "29") (pinfunction "VCC_MIXER_29") (pintype "power_in"))
    )
    (net (code "5") (name "3V3_RF_TX") (class "Default")
      (node (ref "C1") (pin "1") (pinfunction "C1_1") (pintype "passive"))
      (node (ref "C10") (pin "1") (pinfunction "C1_1") (pintype "passive"))
      (node (ref "C12") (pin "1") (pinfunction "C1_1") (pintype "passive"))
      (node (ref "C13") (pin "1") (pinfunction "C1_1") (pintype "passive"))
      (node (ref "C14") (pin "1") (pinfunction "C1_1") (pintype "passive"))
      (node (ref "C16") (pin "1") (pinfunction "C1_1") (pintype "passive"))
      (node (ref "C17") (pin "1") (pinfunction "C1_1") (pintype "passive"))
      (node (ref "C18") (pin "1") (pinfunction "C1_1") (pintype "passive"))
      (node (ref "C2") (pin "1") (pinfunction "C1_1") (pintype "passive"))
      (node (ref "C20") (pin "1") (pinfunction "C1_1") (pintype "passive"))
      (node (ref "C21") (pin "1") (pinfunction "C1_1") (pintype "passive"))
      (node (ref "C22") (pin "1") (pinfunction "C1_1") (pintype "passive"))
      (node (ref "C24") (pin "1") (pinfunction "C1_1") (pintype "passive"))
      (node (ref "C25") (pin "1") (pinfunction "C1_1") (pintype "passive"))
      (node (ref "C26") (pin "1") (pinfunction "C1_1") (pintype "passive"))
      (node (ref "C3") (pin "1") (pinfunction "C1_1") (pintype "passive"))
      (node (ref "C5") (pin "1") (pinfunction "C1_1") (pintype "passive"))
      (node (ref "C6") (pin "1") (pinfunction "C1_1") (pintype "passive"))
      (node (ref "C8") (pin "1") (pinfunction "C1_1") (pintype "passive"))
      (node (ref "C9") (pin "1") (pinfunction "C1_1") (pintype "passive"))
      (node (ref "P24") (pin "PAD_T") (pinfunction "TP_PAD_T") (pintype "input"))
      (node (ref "P25") (pin "PAD_T") (pinfunction "TP_PAD_T") (pintype "input"))
      (node (ref "P26") (pin "PAD_T") (pinfunction "TP_PAD_T") (pintype "input"))
      (node (ref "P27") (pin "PAD_T") (pinfunction "TP_PAD_T") (pintype "input"))
      (node (ref "P28") (pin "PAD_T") (pinfunction "TP_PAD_T") (pintype "input"))
      (node (ref "P29") (pin "PAD_T") (pinfunction "TP_PAD_T") (pintype "input"))
      (node (ref "U3") (pin "11") (pinfunction "VCC2_DRV_11") (pintype "power_in"))
      (node (ref "U3") (pin "17") (pinfunction "VCC_AMP2_17") (pintype "power_in"))
      (node (ref "U3") (pin "19") (pinfunction "VCC_ENV_19") (pintype "power_in"))
      (node (ref "U3") (pin "20") (pinfunction "VCC_AMP1_20") (pintype "power_in"))
      (node (ref "U3") (pin "23") (pinfunction "VCC_BG2_23") (pintype "power_in"))
      (node (ref "U3") (pin "32") (pinfunction "VCC_MIXER_32") (pintype "power_in"))
      (node (ref "U3") (pin "33") (pinfunction "VCC_BG_33") (pintype "power_in"))
      (node (ref "U3") (pin "35") (pinfunction "VCC_QUAD_35") (pintype "power_in"))
      (node (ref "U3") (pin "7") (pinfunction "VCC_DRV_7") (pintype "power_in"))
    )
    (net (code "6") (name "5V0_RF_LO") (class "Default")
      (node (ref "C54") (pin "1") (pinfunction "C1_1") (pintype "passive"))
      (node (ref "C55") (pin "1") (pinfunction "C1_1") (pintype "passive"))
      (node (ref "C56") (pin "1") (pinfunction "C1_1") (pintype "passive"))
      (node (ref "C57") (pin "1") (pinfunction "C1_1") (pintype "passive"))
      (node (ref "C59") (pin "1") (pinfunction "C1_1") (pintype "passive"))
      (node (ref "C60") (pin "1") (pinfunction "C1_1") (pintype "passive"))
      (node (ref "C61") (pin "1") (pinfunction "C1_1") (pintype "passive"))
      (node (ref "C62") (pin "1") (pinfunction "C1_1") (pintype "passive"))
      (node (ref "L2") (pin "1") (pinfunction "1_1") (pintype "passive"))
      (node (ref "L3") (pin "1") (pinfunction "1_1") (pintype "passive"))
      (node (ref "P64") (pin "PAD_T") (pinfunction "TP_PAD_T") (pintype "input"))
      (node (ref "P65") (pin "PAD_T") (pinfunction "TP_PAD_T") (pintype "input"))
      (node (ref "U7") (pin "7") (pinfunction "VD2_7") (pintype "bidirectional"))
      (node (ref "U8") (pin "7") (pinfunction "VD2_7") (pintype "bidirectional"))
    )
    (net (code "7") (name "GND") (class "Default")
      (node (ref "C1") (pin "2") (pinfunction "C2_2") (pintype "passive"))
      (node (ref "C10") (pin "2") (pinfunction "C2_2") (pintype "passive"))
      (node (ref "C11") (pin "2") (pinfunction "C2_2") (pintype "passive"))
      (node (ref "C12") (pin "2") (pinfunction "C2_2") (pintype "passive"))
      (node (ref "C13") (pin "2") (pinfunction "C2_2") (pintype "passive"))
      (node (ref "C14") (pin "2") (pinfunction "C2_2") (pintype "passive"))
      (node (ref "C15") (pin "2") (pinfunction "C2_2") (pintype "passive"))
      (node (ref "C16") (pin "2") (pinfunction "C2_2") (pintype "passive"))
      (node (ref "C17") (pin "2") (pinfunction "C2_2") (pintype "passive"))
      (node (ref "C18") (pin "2") (pinfunction "C2_2") (pintype "passive"))
      (node (ref "C19") (pin "2") (pinfunction "C2_2") (pintype "passive"))
      (node (ref "C2") (pin "2") (pinfunction "C2_2") (pintype "passive"))
      (node (ref "C20") (pin "2") (pinfunction "C2_2") (pintype "passive"))
      (node (ref "C21") (pin "2") (pinfunction "C2_2") (pintype "passive"))
      (node (ref "C22") (pin "2") (pinfunction "C2_2") (pintype "passive"))
      (node (ref "C23") (pin "2") (pinfunction "C2_2") (pintype "passive"))
      (node (ref "C24") (pin "2") (pinfunction "C2_2") (pintype "passive"))
      (node (ref "C25") (pin "2") (pinfunction "C2_2") (pintype "passive"))
      (node (ref "C26") (pin "2") (pinfunction "C2_2") (pintype "passive"))
      (node (ref "C27") (pin "2") (pinfunction "C2_2") (pintype "passive"))
      (node (ref "C28") (pin "2") (pinfunction "C2_2") (pintype "passive"))
      (node (ref "C29") (pin "2") (pinfunction "C2_2") (pintype "passive"))
      (node (ref "C3") (pin "2") (pinfunction "C2_2") (pintype "passive"))
      (node (ref "C30") (pin "2") (pinfunction "C2_2") (pintype "passive"))
      (node (ref "C31") (pin "2") (pinfunction "C2_2") (pintype "passive"))
      (node (ref "C32") (pin "2") (pinfunction "C2_2") (pintype "passive"))
      (node (ref "C33") (pin "2") (pinfunction "C2_2") (pintype "passive"))
      (node (ref "C34") (pin "2") (pinfunction "C2_2") (pintype "passive"))
      (node (ref "C35") (pin "2") (pinfunction "C2_2") (pintype "passive"))
      (node (ref "C36") (pin "2") (pinfunction "C2_2") (pintype "passive"))
      (node (ref "C37") (pin "2") (pinfunction "C2_2") (pintype "passive"))
      (node (ref "C38") (pin "2") (pinfunction "C2_2") (pintype "passive"))
      (node (ref "C39") (pin "2") (pinfunction "C2_2") (pintype "passive"))
      (node (ref "C4") (pin "2") (pinfunction "C2_2") (pintype "passive"))
      (node (ref "C40") (pin "2") (pinfunction "C2_2") (pintype "passive"))
      (node (ref "C41") (pin "2") (pinfunction "C2_2") (pintype "passive"))
      (node (ref "C42") (pin "2") (pinfunction "C2_2") (pintype "passive"))
      (node (ref "C43") (pin "2") (pinfunction "C2_2") (pintype "passive"))
      (node (ref "C44") (pin "2") (pinfunction "C2_2") (pintype "passive"))
      (node (ref "C45") (pin "2") (pinfunction "C2_2") (pintype "passive"))
      (node (ref "C46") (pin "2") (pinfunction "C2_2") (pintype "passive"))
      (node (ref "C47") (pin "2") (pinfunction "C2_2") (pintype "passive"))
      (node (ref "C48") (pin "2") (pinfunction "C2_2") (pintype "passive"))
      (node (ref "C49") (pin "2") (pinfunction "C2_2") (pintype "passive"))
      (node (ref "C5") (pin "2") (pinfunction "C2_2") (pintype "passive"))
      (node (ref "C50") (pin "2") (pinfunction "C2_2") (pintype "passive"))
      (node (ref "C51") (pin "2") (pinfunction "C2_2") (pintype "passive"))
      (node (ref "C52") (pin "2") (pinfunction "C2_2") (pintype "passive"))
      (node (ref "C53") (pin "2") (pinfunction "C2_2") (pintype "passive"))
      (node (ref "C54") (pin "2") (pinfunction "C2_2") (pintype "passive"))
      (node (ref "C55") (pin "2") (pinfunction "C2_2") (pintype "passive"))
      (node (ref "C56") (pin "2") (pinfunction "C2_2") (pintype "passive"))
      (node (ref "C57") (pin "2") (pinfunction "C2_2") (pintype "passive"))
      (node (ref "C58") (pin "2") (pinfunction "C2_2") (pintype "passive"))
      (node (ref "C59") (pin "2") (pinfunction "C2_2") (pintype "passive"))
      (node (ref "C6") (pin "2") (pinfunction "C2_2") (pintype "passive"))
      (node (ref "C60") (pin "2") (pinfunction "C2_2") (pintype "passive"))
      (node (ref "C61") (pin "2") (pinfunction "C2_2") (pintype "passive"))
      (node (ref "C62") (pin "2") (pinfunction "C2_2") (pintype "passive"))
      (node (ref "C63") (pin "2") (pinfunction "C2_2") (pintype "passive"))
      (node (ref "C7") (pin "2") (pinfunction "C2_2") (pintype "passive"))
      (node (ref "C8") (pin "2") (pinfunction "C2_2") (pintype "passive"))
      (node (ref "C9") (pin "2") (pinfunction "C2_2") (pintype "passive"))
      (node (ref "L1") (pin "2") (pinfunction "2_2") (pintype "passive"))
      (node (ref "P11") (pin "PAD_B") (pinfunction "TP_PAD_B") (pintype "input"))
      (node (ref "P11") (pin "PAD_T") (pinfunction "TP_PAD_T") (pintype "input"))
      (node (ref "P12") (pin "PAD_B") (pinfunction "TP_PAD_B") (pintype "input"))
      (node (ref "P12") (pin "PAD_T") (pinfunction "TP_PAD_T") (pintype "input"))
      (node (ref "P13") (pin "PAD_B") (pinfunction "TP_PAD_B") (pintype "input"))
      (node (ref "P13") (pin "PAD_T") (pinfunction "TP_PAD_T") (pintype "input"))
      (node (ref "P14") (pin "PAD_B") (pinfunction "TP_PAD_B") (pintype "input"))
      (node (ref "P14") (pin "PAD_T") (pinfunction "TP_PAD_T") (pintype "input"))
      (node (ref "P15") (pin "PAD_B") (pinfunction "TP_PAD_B") (pintype "input"))
      (node (ref "P15") (pin "PAD_T") (pinfunction "TP_PAD_T") (pintype "input"))
      (node (ref "P16") (pin "PAD_B") (pinfunction "TP_PAD_B") (pintype "input"))
      (node (ref "P16") (pin "PAD_T") (pinfunction "TP_PAD_T") (pintype "input"))
      (node (ref "P17") (pin "PAD_B") (pinfunction "TP_PAD_B") (pintype "input"))
      (node (ref "P17") (pin "PAD_T") (pinfunction "TP_PAD_T") (pintype "input"))
      (node (ref "P18") (pin "PAD_B") (pinfunction "TP_PAD_B") (pintype "input"))
      (node (ref "P18") (pin "PAD_T") (pinfunction "TP_PAD_T") (pintype "input"))
      (node (ref "P19") (pin "PAD_B") (pinfunction "TP_PAD_B") (pintype "input"))
      (node (ref "P19") (pin "PAD_T") (pinfunction "TP_PAD_T") (pintype "input"))
      (node (ref "P20") (pin "PAD_B") (pinfunction "TP_PAD_B") (pintype "input"))
      (node (ref "P20") (pin "PAD_T") (pinfunction "TP_PAD_T") (pintype "input"))
      (node (ref "P21") (pin "PAD_B") (pinfunction "TP_PAD_B") (pintype "input"))
      (node (ref "P21") (pin "PAD_T") (pinfunction "TP_PAD_T") (pintype "input"))
      (node (ref "P30") (pin "PAD_B") (pinfunction "TP_PAD_B") (pintype "input"))
      (node (ref "P30") (pin "PAD_T") (pinfunction "TP_PAD_T") (pintype "input"))
      (node (ref "P31") (pin "PAD_B") (pinfunction "TP_PAD_B") (pintype "input"))
      (node (ref "P31") (pin "PAD_T") (pinfunction "TP_PAD_T") (pintype "input"))
      (node (ref "P32") (pin "PAD_B") (pinfunction "TP_PAD_B") (pintype "input"))
      (node (ref "P32") (pin "PAD_T") (pinfunction "TP_PAD_T") (pintype "input"))
      (node (ref "P40") (pin "PAD_B") (pinfunction "TP_PAD_B") (pintype "input"))
      (node (ref "P40") (pin "PAD_T") (pinfunction "TP_PAD_T") (pintype "input"))
      (node (ref "P41") (pin "PAD_B") (pinfunction "TP_PAD_B") (pintype "input"))
      (node (ref "P41") (pin "PAD_T") (pinfunction "TP_PAD_T") (pintype "input"))
      (node (ref "P42") (pin "PAD_B") (pinfunction "TP_PAD_B") (pintype "input"))
      (node (ref "P42") (pin "PAD_T") (pinfunction "TP_PAD_T") (pintype "input"))
      (node (ref "P43") (pin "PAD_B") (pinfunction "TP_PAD_B") (pintype "input"))
      (node (ref "P43") (pin "PAD_T") (pinfunction "TP_PAD_T") (pintype "input"))
      (node (ref "P44") (pin "PAD_B") (pinfunction "TP_PAD_B") (pintype "input"))
      (node (ref "P44") (pin "PAD_T") (pinfunction "TP_PAD_T") (pintype "input"))
      (node (ref "P45") (pin "PAD_B") (pinfunction "TP_PAD_B") (pintype "input"))
      (node (ref "P45") (pin "PAD_T") (pinfunction "TP_PAD_T") (pintype "input"))
      (node (ref "P46") (pin "PAD_B") (pinfunction "TP_PAD_B") (pintype "input"))
      (node (ref "P46") (pin "PAD_T") (pinfunction "TP_PAD_T") (pintype "input"))
      (node (ref "P47") (pin "PAD_B") (pinfunction "TP_PAD_B") (pintype "input"))
      (node (ref "P47") (pin "PAD_T") (pinfunction "TP_PAD_T") (pintype "input"))
      (node (ref "P48") (pin "PAD_B") (pinfunction "TP_PAD_B") (pintype "input"))
      (node (ref "P48") (pin "PAD_T") (pinfunction "TP_PAD_T") (pintype "input"))
      (node (ref "P49") (pin "PAD_B") (pinfunction "TP_PAD_B") (pintype "input"))
      (node (ref "P49") (pin "PAD_T") (pinfunction "TP_PAD_T") (pintype "input"))
      (node (ref "P50") (pin "PAD_B") (pinfunction "TP_PAD_B") (pintype "input"))
      (node (ref "P50") (pin "PAD_T") (pinfunction "TP_PAD_T") (pintype "input"))
      (node (ref "P51") (pin "PAD_B") (pinfunction "TP_PAD_B") (pintype "input"))
      (node (ref "P51") (pin "PAD_T") (pinfunction "TP_PAD_T") (pintype "input"))
      (node (ref "P61") (pin "PAD_B") (pinfunction "TP_PAD_B") (pintype "input"))
      (node (ref "P61") (pin "PAD_T") (pinfunction "TP_PAD_T") (pintype "input"))
      (node (ref "P62") (pin "PAD_B") (pinfunction "TP_PAD_B") (pintype "input"))
      (node (ref "P62") (pin "PAD_T") (pinfunction "TP_PAD_T") (pintype "input"))
      (node (ref "P63") (pin "PAD_B") (pinfunction "TP_PAD_B") (pintype "input"))
      (node (ref "P63") (pin "PAD_T") (pinfunction "TP_PAD_T") (pintype "input"))
      (node (ref "P66") (pin "PAD_B") (pinfunction "TP_PAD_B") (pintype "input"))
      (node (ref "P66") (pin "PAD_T") (pinfunction "TP_PAD_T") (pintype "input"))
      (node (ref "P67") (pin "PAD_B") (pinfunction "TP_PAD_B") (pintype "input"))
      (node (ref "P67") (pin "PAD_T") (pinfunction "TP_PAD_T") (pintype "input"))
      (node (ref "R1") (pin "1") (pinfunction "1_1") (pintype "passive"))
      (node (ref "R11") (pin "1") (pinfunction "1_1") (pintype "passive"))
      (node (ref "R12") (pin "1") (pinfunction "1_1") (pintype "passive"))
      (node (ref "R14") (pin "1") (pinfunction "1_1") (pintype "passive"))
      (node (ref "R15") (pin "1") (pinfunction "1_1") (pintype "passive"))
      (node (ref "R16") (pin "1") (pinfunction "1_1") (pintype "passive"))
      (node (ref "R17") (pin "1") (pinfunction "1_1") (pintype "passive"))
      (node (ref "R19") (pin "1") (pinfunction "1_1") (pintype "passive"))
      (node (ref "R20") (pin "1") (pinfunction "1_1") (pintype "passive"))
      (node (ref "R3") (pin "1") (pinfunction "1_1") (pintype "passive"))
      (node (ref "R5") (pin "1") (pinfunction "1_1") (pintype "passive"))
      (node (ref "R6") (pin "1") (pinfunction "1_1") (pintype "passive"))
      (node (ref "R7") (pin "1") (pinfunction "1_1") (pintype "passive"))
      (node (ref "R8") (pin "1") (pinfunction "1_1") (pintype "passive"))
      (node (ref "R9") (pin "1") (pinfunction "1_1") (pintype "passive"))
      (node (ref "RFCON1") (pin "P$1") (pinfunction "GND_P$1") (pintype "bidirectional"))
      (node (ref "RFCON1") (pin "P$2") (pinfunction "GND_P$2") (pintype "bidirectional"))
      (node (ref "RFCON2") (pin "GND@1") (pinfunction "GND_GND@1") (pintype "bidirectional"))
      (node (ref "RFCON2") (pin "GND@2") (pinfunction "GND_GND@2") (pintype "bidirectional"))
      (node (ref "RFCON3") (pin "P$1") (pinfunction "GND_P$1") (pintype "bidirectional"))
      (node (ref "RFCON3") (pin "P$2") (pinfunction "GND_P$2") (pintype "bidirectional"))
      (node (ref "RFCON4") (pin "GND@1") (pinfunction "GND_GND@1") (pintype "bidirectional"))
      (node (ref "RFCON4") (pin "GND@2") (pinfunction "GND_GND@2") (pintype "bidirectional"))
      (node (ref "RFCON5") (pin "P$1") (pinfunction "GND_P$1") (pintype "bidirectional"))
      (node (ref "RFCON5") (pin "P$2") (pinfunction "GND_P$2") (pintype "bidirectional"))
      (node (ref "U1") (pin "2") (pinfunction "GND_2") (pintype "bidirectional"))
      (node (ref "U1") (pin "4") (pinfunction "GND_4") (pintype "bidirectional"))
      (node (ref "U2") (pin "2") (pinfunction "GND_2") (pintype "bidirectional"))
      (node (ref "U2") (pin "5") (pinfunction "GND_5") (pintype "bidirectional"))
      (node (ref "U3") (pin "10") (pinfunction "GND_10") (pintype "bidirectional"))
      (node (ref "U3") (pin "27") (pinfunction "GND_27") (pintype "bidirectional"))
      (node (ref "U3") (pin "36") (pinfunction "GND_36") (pintype "bidirectional"))
      (node (ref "U3") (pin "39") (pinfunction "GND_39") (pintype "bidirectional"))
      (node (ref "U3") (pin "41") (pinfunction "GND_41") (pintype "bidirectional"))
      (node (ref "U3") (pin "8") (pinfunction "GND_8") (pintype "bidirectional"))
      (node (ref "U4") (pin "2") (pinfunction "GND_2") (pintype "bidirectional"))
      (node (ref "U4") (pin "4") (pinfunction "GND_4") (pintype "bidirectional"))
      (node (ref "U5") (pin "2") (pinfunction "GND_2") (pintype "bidirectional"))
      (node (ref "U5") (pin "5") (pinfunction "GND_5") (pintype "bidirectional"))
      (node (ref "U6") (pin "13") (pinfunction "GND_13") (pintype "bidirectional"))
      (node (ref "U6") (pin "17") (pinfunction "GND_17") (pintype "bidirectional"))
      (node (ref "U6") (pin "19") (pinfunction "GND_19") (pintype "bidirectional"))
      (node (ref "U6") (pin "25") (pinfunction "GND_25") (pintype "bidirectional"))
      (node (ref "U6") (pin "28") (pinfunction "GND_28") (pintype "bidirectional"))
      (node (ref "U6") (pin "33") (pinfunction "GND_33") (pintype "bidirectional"))
      (node (ref "U6") (pin "5") (pinfunction "GND_5") (pintype "bidirectional"))
      (node (ref "U7") (pin "1") (pinfunction "GND_1") (pintype "bidirectional"))
      (node (ref "U7") (pin "6") (pinfunction "GND_6") (pintype "bidirectional"))
      (node (ref "U7") (pin "9") (pinfunction "GND_9") (pintype "bidirectional"))
      (node (ref "U8") (pin "1") (pinfunction "GND_1") (pintype "bidirectional"))
      (node (ref "U8") (pin "6") (pinfunction "GND_6") (pintype "bidirectional"))
      (node (ref "U8") (pin "9") (pinfunction "GND_9") (pintype "bidirectional"))
    )
    (net (code "8") (name "Net-(C58-C1)") (class "Default")
      (node (ref "C58") (pin "1") (pinfunction "C1_1") (pintype "passive"))
      (node (ref "L2") (pin "2") (pinfunction "2_2") (pintype "passive"))
      (node (ref "U7") (pin "8") (pinfunction "VD1_8") (pintype "bidirectional"))
    )
    (net (code "9") (name "Net-(C63-C1)") (class "Default")
      (node (ref "C63") (pin "1") (pinfunction "C1_1") (pintype "passive"))
      (node (ref "L3") (pin "2") (pinfunction "2_2") (pintype "passive"))
      (node (ref "U8") (pin "8") (pinfunction "VD1_8") (pintype "bidirectional"))
    )
    (net (code "10") (name "Net-(R18-Pad1)") (class "Default")
      (node (ref "R18") (pin "1") (pinfunction "1_1") (pintype "passive"))
      (node (ref "R19") (pin "2") (pinfunction "2_2") (pintype "passive"))
      (node (ref "R20") (pin "2") (pinfunction "2_2") (pintype "passive"))
      (node (ref "R21") (pin "2") (pinfunction "2_2") (pintype "passive"))
    )
    (net (code "11") (name "Net-(R21-Pad1)") (class "Default")
      (node (ref "R21") (pin "1") (pinfunction "1_1") (pintype "passive"))
      (node (ref "R22") (pin "2") (pinfunction "2_2") (pintype "passive"))
      (node (ref "R23") (pin "2") (pinfunction "2_2") (pintype "passive"))
    )
    (net (code "12") (name "Net-(RFCON1-SIGNAL)") (class "Default")
      (node (ref "RFCON1") (pin "P$3") (pinfunction "SIGNAL_P$3") (pintype "bidirectional"))
      (node (ref "U1") (pin "1") (pinfunction "RFIN_1") (pintype "bidirectional"))
    )
    (net (code "13") (name "Net-(RFCON2-SIGNAL)") (class "Default")
      (node (ref "RFCON2") (pin "SIG") (pinfunction "SIGNAL_SIG") (pintype "bidirectional"))
      (node (ref "U3") (pin "9") (pinfunction "RF_9") (pintype "input"))
    )
    (net (code "14") (name "Net-(RFCON3-SIGNAL)") (class "Default")
      (node (ref "RFCON3") (pin "P$3") (pinfunction "SIGNAL_P$3") (pintype "bidirectional"))
      (node (ref "U4") (pin "3") (pinfunction "RFOUT_3") (pintype "bidirectional"))
    )
    (net (code "15") (name "Net-(RFCON4-SIGNAL)") (class "Default")
      (node (ref "RFCON4") (pin "SIG") (pinfunction "SIGNAL_SIG") (pintype "bidirectional"))
      (node (ref "U6") (pin "18") (pinfunction "RF_IN_18") (pintype "input"))
    )
    (net (code "16") (name "Net-(RFCON5-SIGNAL)") (class "Default")
      (node (ref "R10") (pin "2") (pinfunction "2_2") (pintype "passive"))
      (node (ref "RFCON5") (pin "P$3") (pinfunction "SIGNAL_P$3") (pintype "bidirectional"))
    )
    (net (code "17") (name "Net-(U1-RFOUT)") (class "Default")
      (node (ref "U1") (pin "3") (pinfunction "RFOUT_3") (pintype "bidirectional"))
      (node (ref "U2") (pin "1") (pinfunction "SUM_1") (pintype "bidirectional"))
    )
    (net (code "18") (name "Net-(U2-0DEG)") (class "Default")
      (node (ref "U2") (pin "4") (pinfunction "0DEG_4") (pintype "bidirectional"))
      (node (ref "U3") (pin "30") (pinfunction "IF_I_30") (pintype "input"))
    )
    (net (code "19") (name "Net-(U2-ISO)") (class "Default")
      (node (ref "R1") (pin "2") (pinfunction "2_2") (pintype "passive"))
      (node (ref "U2") (pin "3") (pinfunction "ISO_3") (pintype "bidirectional"))
    )
    (net (code "20") (name "Net-(U2-P90DEG)") (class "Default")
      (node (ref "U2") (pin "6") (pinfunction "P90DEG_6") (pintype "bidirectional"))
      (node (ref "U3") (pin "24") (pinfunction "IF_Q_24") (pintype "input"))
    )
    (net (code "21") (name "Net-(U3-BG_RBIAS1)") (class "Default")
      (node (ref "R5") (pin "2") (pinfunction "2_2") (pintype "passive"))
      (node (ref "U3") (pin "34") (pinfunction "BG_RBIAS1_34") (pintype "bidirectional"))
    )
    (net (code "22") (name "Net-(U3-BG_RBIAS2)") (class "Default")
      (node (ref "R3") (pin "2") (pinfunction "2_2") (pintype "passive"))
      (node (ref "U3") (pin "6") (pinfunction "BG_RBIAS2_6") (pintype "bidirectional"))
    )
    (net (code "23") (name "Net-(U3-LON)") (class "Default")
      (node (ref "R6") (pin "2") (pinfunction "2_2") (pintype "passive"))
      (node (ref "U3") (pin "37") (pinfunction "LON_37") (pintype "input"))
    )
    (net (code "24") (name "Net-(U3-VCTRL1)") (class "Default")
      (node (ref "R2") (pin "2") (pinfunction "2_2") (pintype "passive"))
      (node (ref "U3") (pin "15") (pinfunction "VCTRL1_15") (pintype "input"))
    )
    (net (code "25") (name "Net-(U3-VCTRL2)") (class "Default")
      (node (ref "R4") (pin "2") (pinfunction "2_2") (pintype "passive"))
      (node (ref "U3") (pin "16") (pinfunction "VCTRL2_16") (pintype "input"))
    )
    (net (code "26") (name "Net-(U4-RFIN)") (class "Default")
      (node (ref "U4") (pin "1") (pinfunction "RFIN_1") (pintype "bidirectional"))
      (node (ref "U5") (pin "1") (pinfunction "SUM_1") (pintype "bidirectional"))
    )
    (net (code "27") (name "Net-(U5-0DEG)") (class "Default")
      (node (ref "U5") (pin "4") (pinfunction "0DEG_4") (pintype "bidirectional"))
      (node (ref "U6") (pin "6") (pinfunction "IF_Q_6") (pintype "input"))
    )
    (net (code "28") (name "Net-(U5-ISO)") (class "Default")
      (node (ref "R7") (pin "2") (pinfunction "2_2") (pintype "passive"))
      (node (ref "U5") (pin "3") (pinfunction "ISO_3") (pintype "bidirectional"))
    )
    (net (code "29") (name "Net-(U5-P90DEG)") (class "Default")
      (node (ref "U5") (pin "6") (pinfunction "P90DEG_6") (pintype "bidirectional"))
      (node (ref "U6") (pin "4") (pinfunction "IF_I_4") (pintype "input"))
    )
    (net (code "30") (name "Net-(U6-BG_RBIAS)") (class "Default")
      (node (ref "R8") (pin "2") (pinfunction "2_2") (pintype "passive"))
      (node (ref "U6") (pin "23") (pinfunction "BG_RBIAS_23") (pintype "bidirectional"))
    )
    (net (code "31") (name "Net-(U6-LO_N)") (class "Default")
      (node (ref "R9") (pin "2") (pinfunction "2_2") (pintype "passive"))
      (node (ref "U6") (pin "26") (pinfunction "LO_N_26") (pintype "input"))
    )
    (net (code "32") (name "Net-(U7-RFIN)") (class "Default")
      (node (ref "L1") (pin "1") (pinfunction "1_1") (pintype "passive"))
      (node (ref "R10") (pin "1") (pinfunction "1_1") (pintype "passive"))
      (node (ref "U7") (pin "2") (pinfunction "RFIN_2") (pintype "bidirectional"))
    )
    (net (code "33") (name "Net-(U7-RFOUT)") (class "Default")
      (node (ref "R11") (pin "2") (pinfunction "2_2") (pintype "passive"))
      (node (ref "R12") (pin "2") (pinfunction "2_2") (pintype "passive"))
      (node (ref "R13") (pin "2") (pinfunction "2_2") (pintype "passive"))
      (node (ref "U7") (pin "5") (pinfunction "RFOUT_5") (pintype "bidirectional"))
    )
    (net (code "34") (name "Net-(U8-RFIN)") (class "Default")
      (node (ref "R13") (pin "1") (pinfunction "1_1") (pintype "passive"))
      (node (ref "R14") (pin "2") (pinfunction "2_2") (pintype "passive"))
      (node (ref "R15") (pin "2") (pinfunction "2_2") (pintype "passive"))
      (node (ref "U8") (pin "2") (pinfunction "RFIN_2") (pintype "bidirectional"))
    )
    (net (code "35") (name "Net-(U8-RFOUT)") (class "Default")
      (node (ref "R16") (pin "2") (pinfunction "2_2") (pintype "passive"))
      (node (ref "R17") (pin "2") (pinfunction "2_2") (pintype "passive"))
      (node (ref "R18") (pin "2") (pinfunction "2_2") (pintype "passive"))
      (node (ref "U8") (pin "5") (pinfunction "RFOUT_5") (pintype "bidirectional"))
    )
    (net (code "36") (name "RX_GAIN_VCTRL") (class "Default")
      (node (ref "P34") (pin "PAD_T") (pinfunction "TP_PAD_T") (pintype "input"))
      (node (ref "U6") (pin "14") (pinfunction "VCTRL_14") (pintype "input"))
    )
    (net (code "37") (name "RX_LO") (class "Default")
      (node (ref "R22") (pin "1") (pinfunction "1_1") (pintype "passive"))
      (node (ref "U6") (pin "27") (pinfunction "LO_P_27") (pintype "input"))
    )
    (net (code "38") (name "RX_PWR_VDET") (class "Default")
      (node (ref "P33") (pin "PAD_T") (pinfunction "TP_PAD_T") (pintype "input"))
      (node (ref "U6") (pin "11") (pinfunction "VDET_11") (pintype "input"))
    )
    (net (code "39") (name "RX_SPI_SCLK") (class "Default")
      (node (ref "P36") (pin "PAD_T") (pinfunction "TP_PAD_T") (pintype "input"))
      (node (ref "U6") (pin "31") (pinfunction "SCLK_31") (pintype "input"))
    )
    (net (code "40") (name "RX_SPI_SDI") (class "Default")
      (node (ref "P38") (pin "PAD_T") (pinfunction "TP_PAD_T") (pintype "input"))
      (node (ref "U6") (pin "32") (pinfunction "SDI_32") (pintype "input"))
    )
    (net (code "41") (name "RX_SPI_SDO") (class "Default")
      (node (ref "P37") (pin "PAD_T") (pinfunction "TP_PAD_T") (pintype "input"))
      (node (ref "U6") (pin "9") (pinfunction "SDO_9") (pintype "output"))
    )
    (net (code "42") (name "TX_GAIN_VCTRL1") (class "Default")
      (node (ref "P1") (pin "PAD_T") (pinfunction "TP_PAD_T") (pintype "input"))
      (node (ref "R2") (pin "1") (pinfunction "1_1") (pintype "passive"))
    )
    (net (code "43") (name "TX_GAIN_VCTRL2") (class "Default")
      (node (ref "P2") (pin "PAD_T") (pinfunction "TP_PAD_T") (pintype "input"))
      (node (ref "R4") (pin "1") (pinfunction "1_1") (pintype "passive"))
    )
    (net (code "44") (name "TX_LO") (class "Default")
      (node (ref "R23") (pin "1") (pinfunction "1_1") (pintype "passive"))
      (node (ref "U3") (pin "38") (pinfunction "LOP_38") (pintype "input"))
    )
    (net (code "45") (name "TX_PWR_VDET_N") (class "Default")
      (node (ref "P4") (pin "PAD_T") (pinfunction "TP_PAD_T") (pintype "input"))
      (node (ref "U3") (pin "21") (pinfunction "VENV_N_21") (pintype "input"))
    )
    (net (code "46") (name "TX_PWR_VDET_P") (class "Default")
      (node (ref "P3") (pin "PAD_T") (pinfunction "TP_PAD_T") (pintype "input"))
      (node (ref "U3") (pin "22") (pinfunction "VENV_P_22") (pintype "input"))
    )
    (net (code "47") (name "TX_SPI_SCLK") (class "Default")
      (node (ref "P7") (pin "PAD_T") (pinfunction "TP_PAD_T") (pintype "input"))
      (node (ref "U3") (pin "3") (pinfunction "SCLK_3") (pintype "input"))
    )
    (net (code "48") (name "TX_SPI_SDI") (class "Default")
      (node (ref "P9") (pin "PAD_T") (pinfunction "TP_PAD_T") (pintype "input"))
      (node (ref "U3") (pin "4") (pinfunction "SDI_4") (pintype "input"))
    )
    (net (code "49") (name "TX_SPI_SDO") (class "Default")
      (node (ref "P8") (pin "PAD_T") (pinfunction "TP_PAD_T") (pintype "input"))
      (node (ref "U3") (pin "5") (pinfunction "SDO_5") (pintype "output"))
    )
    (net (code "50") (name "unconnected-(U3-I_N-Pad29)") (class "Default")
      (node (ref "U3") (pin "29") (pinfunction "I_N_29") (pintype "input"))
    )
    (net (code "51") (name "unconnected-(U3-I_P-Pad28)") (class "Default")
      (node (ref "U3") (pin "28") (pinfunction "I_P_28") (pintype "input"))
    )
    (net (code "52") (name "unconnected-(U3-Q_N-Pad25)") (class "Default")
      (node (ref "U3") (pin "25") (pinfunction "Q_N_25") (pintype "input"))
    )
    (net (code "53") (name "unconnected-(U3-Q_P-Pad26)") (class "Default")
      (node (ref "U3") (pin "26") (pinfunction "Q_P_26") (pintype "input"))
    )
    (net (code "54") (name "unconnected-(U6-I_N-Pad3)") (class "Default")
      (node (ref "U6") (pin "3") (pinfunction "I_N_3") (pintype "input"))
    )
    (net (code "55") (name "unconnected-(U6-I_P-Pad2)") (class "Default")
      (node (ref "U6") (pin "2") (pinfunction "I_P_2") (pintype "input"))
    )
    (net (code "56") (name "unconnected-(U6-Q_N-Pad7)") (class "Default")
      (node (ref "U6") (pin "7") (pinfunction "Q_N_7") (pintype "input"))
    )
    (net (code "57") (name "unconnected-(U6-Q_P-Pad8)") (class "Default")
      (node (ref "U6") (pin "8") (pinfunction "Q_P_8") (pintype "input"))
    )
    (net (code "58") (name "~{RX_RST}") (class "Default")
      (node (ref "P39") (pin "PAD_T") (pinfunction "TP_PAD_T") (pintype "input"))
      (node (ref "U6") (pin "22") (pinfunction "RST_22") (pintype "input"))
    )
    (net (code "59") (name "~{RX_SPI_SEN}") (class "Default")
      (node (ref "P35") (pin "PAD_T") (pinfunction "TP_PAD_T") (pintype "input"))
      (node (ref "U6") (pin "1") (pinfunction "~{SEN}_1") (pintype "input"))
    )
    (net (code "60") (name "~{TX_RST}") (class "Default")
      (node (ref "P10") (pin "PAD_T") (pinfunction "TP_PAD_T") (pintype "input"))
      (node (ref "U3") (pin "1") (pinfunction "RST_1") (pintype "input"))
    )
    (net (code "61") (name "~{TX_SPI_SEN2}") (class "Default")
      (node (ref "P5") (pin "PAD_T") (pinfunction "TP_PAD_T") (pintype "input"))
      (node (ref "U3") (pin "18") (pinfunction "~{SEN2}_18") (pintype "input"))
    )
    (net (code "62") (name "~{TX_SPI_SEN}") (class "Default")
      (node (ref "P6") (pin "PAD_T") (pinfunction "TP_PAD_T") (pintype "input"))
      (node (ref "U3") (pin "40") (pinfunction "~{SEN}_40") (pintype "input"))
    )
  )
)
